# ClockRecovery.net
KiCad netlist of a schematic drawn in Altium Designer
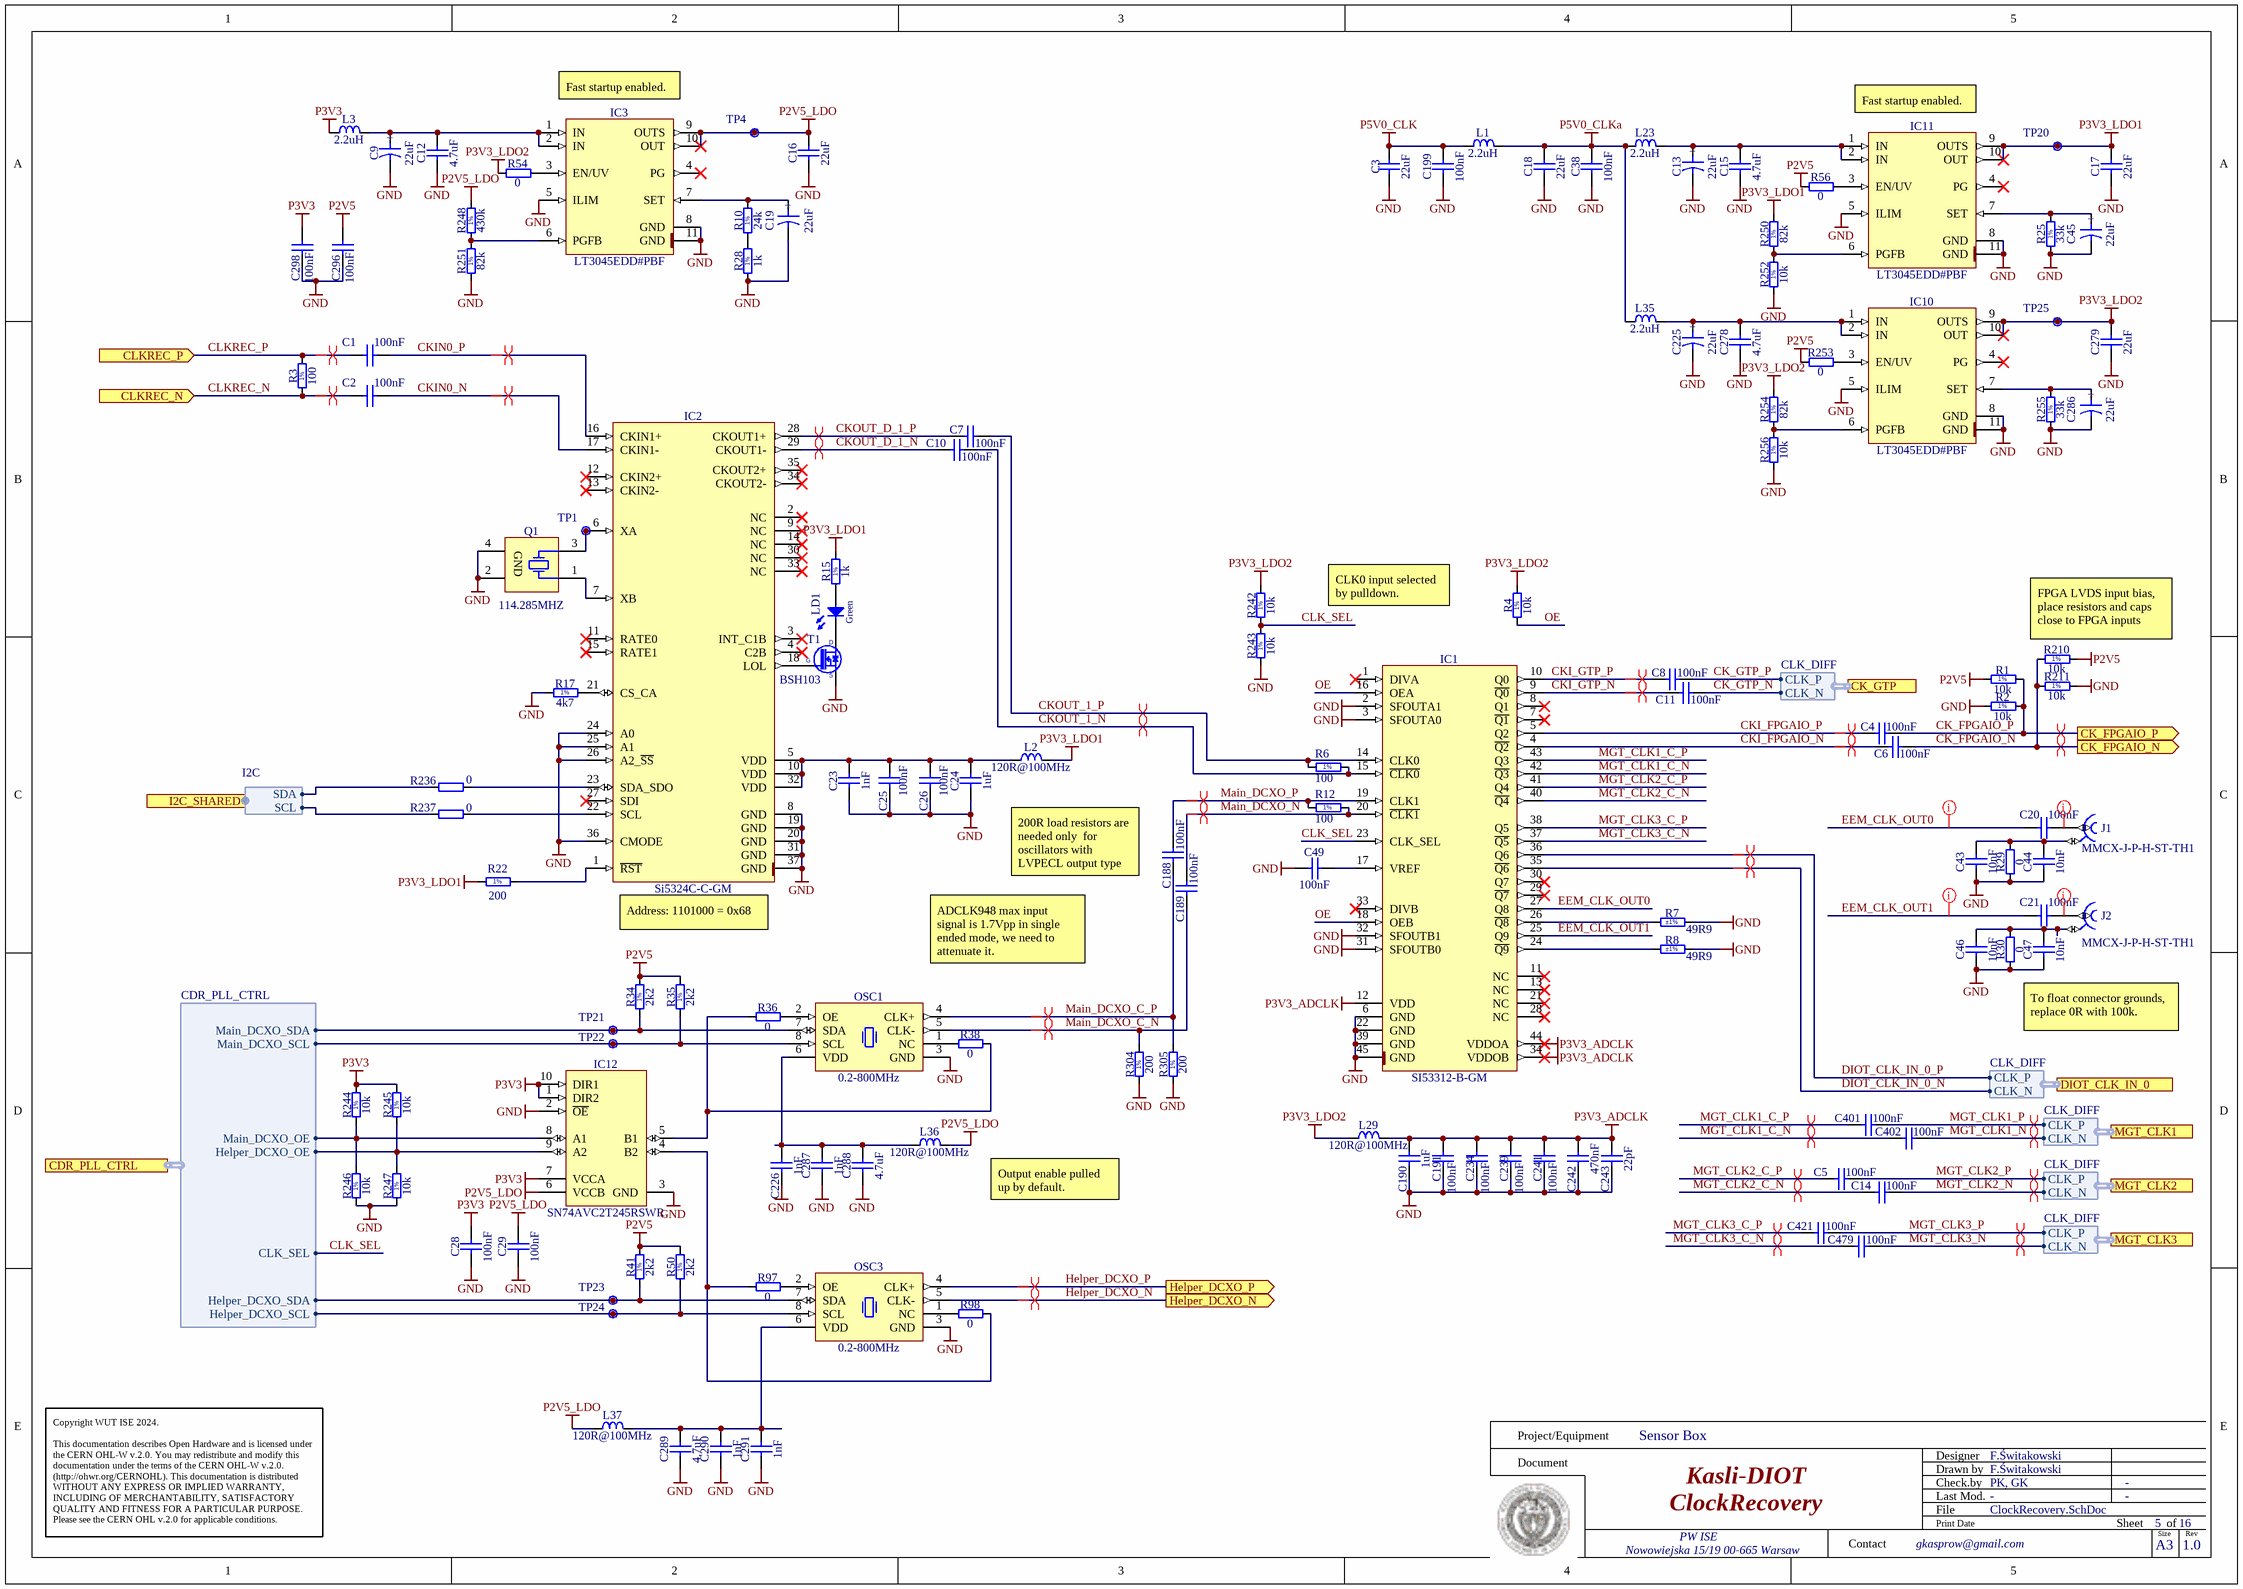
[diagram p0: ClockRecovery.SchDoc]

(export (version "E")
  (design (tool "Eeschema 10.0.6"))
  (components
    (comp (ref "C1")
      (value "100nF")
      (footprint "CAPC0603X33N")
      (description "Non-polarised capacitor")
      (fields
        (field (name "PART NUMBER") "CC0201_100NF_6.3V_10%_X5R")
        (field (name "VOLTAGE") "6.3V")
        (field (name "AUTHOR") "CERN DEM JLC")
      )
      (libsource (lib "Capacitors") (part "Capacitor - non polarized"))
    )
    (comp (ref "C2")
      (value "100nF")
      (footprint "CAPC0603X33N")
      (description "Non-polarised capacitor")
      (fields
        (field (name "PART NUMBER") "CC0201_100NF_6.3V_10%_X5R")
        (field (name "VOLTAGE") "6.3V")
        (field (name "AUTHOR") "CERN DEM JLC")
      )
      (libsource (lib "Capacitors") (part "Capacitor - non polarized"))
    )
    (comp (ref "C3")
      (value "22uF")
      (footprint "CAPC2012X135N")
      (description "Non-polarised capacitor")
      (fields
        (field (name "MANUFACTURER PART NUMBER") "CC0805_22UF_16V_10%_X5R")
        (field (name "MANUFACTURER") "GENERIC")
        (field (name "AUTHOR") "CERN DEM JLC")
      )
      (libsource (lib "Capacitors") (part "Capacitor - non polarized"))
    )
    (comp (ref "C4")
      (value "100nF")
      (footprint "CAPC0603X33N")
      (description "Non-polarised capacitor")
      (fields
        (field (name "PART NUMBER") "CC0201_100NF_6.3V_10%_X5R")
        (field (name "VOLTAGE") "6.3V")
        (field (name "AUTHOR") "CERN DEM JLC")
      )
      (libsource (lib "Capacitors") (part "Capacitor - non polarized"))
    )
    (comp (ref "C5")
      (value "100nF")
      (footprint "CAPC0603X33N")
      (description "Non-polarised capacitor")
      (fields
        (field (name "PART NUMBER") "CC0201_100NF_6.3V_10%_X5R")
        (field (name "VOLTAGE") "6.3V")
        (field (name "AUTHOR") "CERN DEM JLC")
      )
      (libsource (lib "Capacitors") (part "Capacitor - non polarized"))
    )
    (comp (ref "C6")
      (value "100nF")
      (footprint "CAPC0603X33N")
      (description "Non-polarised capacitor")
      (fields
        (field (name "PART NUMBER") "CC0201_100NF_6.3V_10%_X5R")
        (field (name "VOLTAGE") "6.3V")
        (field (name "AUTHOR") "CERN DEM JLC")
      )
      (libsource (lib "Capacitors") (part "Capacitor - non polarized"))
    )
    (comp (ref "C7")
      (value "100nF")
      (footprint "CAPC0603X33N")
      (description "Non-polarised capacitor")
      (fields
        (field (name "PART NUMBER") "CC0201_100NF_6.3V_10%_X5R")
        (field (name "VOLTAGE") "6.3V")
        (field (name "AUTHOR") "CERN DEM JLC")
      )
      (libsource (lib "Capacitors") (part "Capacitor - non polarized"))
    )
    (comp (ref "C8")
      (value "100nF")
      (footprint "CAPC0603X33N")
      (description "Non-polarised capacitor")
      (fields
        (field (name "PART NUMBER") "CC0201_100NF_6.3V_10%_X5R")
        (field (name "VOLTAGE") "6.3V")
        (field (name "AUTHOR") "CERN DEM JLC")
      )
      (libsource (lib "Capacitors") (part "Capacitor - non polarized"))
    )
    (comp (ref "C9")
      (value "22uF")
      (footprint "CAPMP3216X180N")
      (description "Polarised capacitor")
      (fields
        (field (name "PART NUMBER") "CTE3216-18_22UF_6.3V_10%_LESR0900")
        (field (name "VOLTAGE") "6.3V")
        (field (name "AUTHOR") "CERN DEM JLC")
      )
      (libsource (lib "Capacitors") (part "Capacitor - polarized"))
    )
    (comp (ref "C10")
      (value "100nF")
      (footprint "CAPC0603X33N")
      (description "Non-polarised capacitor")
      (fields
        (field (name "PART NUMBER") "CC0201_100NF_6.3V_10%_X5R")
        (field (name "VOLTAGE") "6.3V")
        (field (name "AUTHOR") "CERN DEM JLC")
      )
      (libsource (lib "Capacitors") (part "Capacitor - non polarized"))
    )
    (comp (ref "C11")
      (value "100nF")
      (footprint "CAPC0603X33N")
      (description "Non-polarised capacitor")
      (fields
        (field (name "PART NUMBER") "CC0201_100NF_6.3V_10%_X5R")
        (field (name "VOLTAGE") "6.3V")
        (field (name "AUTHOR") "CERN DEM JLC")
      )
      (libsource (lib "Capacitors") (part "Capacitor - non polarized"))
    )
    (comp (ref "C12")
      (value "4.7uF")
      (footprint "CAPC1005X55N")
      (description "Non-polarised capacitor")
      (fields
        (field (name "PART NUMBER") "CC0402_4.7UF_6.3V_20%_X5R")
        (field (name "VOLTAGE") "6.3V")
        (field (name "AUTHOR") "CERN DEM JLC")
      )
      (libsource (lib "Capacitors") (part "Capacitor - non polarized"))
    )
    (comp (ref "C13")
      (value "22uF")
      (footprint "CAPMP3216X180N")
      (description "Polarised capacitor")
      (fields
        (field (name "PART NUMBER") "CTE3216-18_22UF_6.3V_10%_LESR0900")
        (field (name "VOLTAGE") "6.3V")
        (field (name "AUTHOR") "CERN DEM JLC")
      )
      (libsource (lib "Capacitors") (part "Capacitor - polarized"))
    )
    (comp (ref "C14")
      (value "100nF")
      (footprint "CAPC0603X33N")
      (description "Non-polarised capacitor")
      (fields
        (field (name "PART NUMBER") "CC0201_100NF_6.3V_10%_X5R")
        (field (name "VOLTAGE") "6.3V")
        (field (name "AUTHOR") "CERN DEM JLC")
      )
      (libsource (lib "Capacitors") (part "Capacitor - non polarized"))
    )
    (comp (ref "C15")
      (value "4.7uF")
      (footprint "CAPC1005X55N")
      (description "Non-polarised capacitor")
      (fields
        (field (name "PART NUMBER") "CC0402_4.7UF_6.3V_20%_X5R")
        (field (name "VOLTAGE") "6.3V")
        (field (name "AUTHOR") "CERN DEM JLC")
      )
      (libsource (lib "Capacitors") (part "Capacitor - non polarized"))
    )
    (comp (ref "C16")
      (value "22uF")
      (footprint "CAPC1709X100N")
      (description "Non-polarised capacitor")
      (fields
        (field (name "PART NUMBER") "CC0603_22UF_6.3V_20%_X5R")
        (field (name "VOLTAGE") "6.3V")
        (field (name "AUTHOR") "CERN DEM JLC")
      )
      (libsource (lib "Capacitors") (part "Capacitor - non polarized"))
    )
    (comp (ref "C17")
      (value "22uF")
      (footprint "CAPC1709X100N")
      (description "Non-polarised capacitor")
      (fields
        (field (name "PART NUMBER") "CC0603_22UF_6.3V_20%_X5R")
        (field (name "VOLTAGE") "6.3V")
        (field (name "AUTHOR") "CERN DEM JLC")
      )
      (libsource (lib "Capacitors") (part "Capacitor - non polarized"))
    )
    (comp (ref "C18")
      (value "22uF")
      (footprint "CAPC2012X135N")
      (description "Non-polarised capacitor")
      (fields
        (field (name "MANUFACTURER PART NUMBER") "CC0805_22UF_16V_10%_X5R")
        (field (name "MANUFACTURER") "GENERIC")
        (field (name "AUTHOR") "CERN DEM JLC")
      )
      (libsource (lib "Capacitors") (part "Capacitor - non polarized"))
    )
    (comp (ref "C19")
      (value "22uF")
      (footprint "CAPMP3216X180N")
      (description "Polarised capacitor")
      (fields
        (field (name "PART NUMBER") "CTE3216-18_22UF_6.3V_10%_LESR0900")
        (field (name "VOLTAGE") "6.3V")
        (field (name "AUTHOR") "CERN DEM JLC")
      )
      (libsource (lib "Capacitors") (part "Capacitor - polarized"))
    )
    (comp (ref "C20")
      (value "100nF")
      (footprint "CAPC0603X33N")
      (description "Non-polarised capacitor")
      (fields
        (field (name "PART NUMBER") "CC0201_100NF_6.3V_10%_X5R")
        (field (name "VOLTAGE") "6.3V")
        (field (name "AUTHOR") "CERN DEM JLC")
      )
      (libsource (lib "Capacitors") (part "Capacitor - non polarized"))
    )
    (comp (ref "C21")
      (value "100nF")
      (footprint "CAPC0603X33N")
      (description "Non-polarised capacitor")
      (fields
        (field (name "PART NUMBER") "CC0201_100NF_6.3V_10%_X5R")
        (field (name "VOLTAGE") "6.3V")
        (field (name "AUTHOR") "CERN DEM JLC")
      )
      (libsource (lib "Capacitors") (part "Capacitor - non polarized"))
    )
    (comp (ref "C23")
      (value "1nF")
      (footprint "CAPC1005X55N")
      (description "Non-polarised capacitor")
      (fields
        (field (name "PART NUMBER") "CC0402_1NF_50V_10%_X7R")
        (field (name "VOLTAGE") "50V")
        (field (name "AUTHOR") "CERN DEM JLC")
      )
      (libsource (lib "Capacitors") (part "Capacitor - non polarized"))
    )
    (comp (ref "C24")
      (value "1uF")
      (footprint "CAPC1005X55N")
      (description "Non-polarised capacitor")
      (fields
        (field (name "PART NUMBER") "CC0402_1UF_16V_10%_X5R")
        (field (name "VOLTAGE") "16V")
        (field (name "AUTHOR") "CERN DEM JLC")
      )
      (libsource (lib "Capacitors") (part "Capacitor - non polarized"))
    )
    (comp (ref "C25")
      (value "100nF")
      (footprint "CAPC0603X33N")
      (description "Non-polarised capacitor")
      (fields
        (field (name "PART NUMBER") "CC0201_100NF_6.3V_10%_X5R")
        (field (name "VOLTAGE") "6.3V")
        (field (name "AUTHOR") "CERN DEM JLC")
      )
      (libsource (lib "Capacitors") (part "Capacitor - non polarized"))
    )
    (comp (ref "C26")
      (value "100nF")
      (footprint "CAPC0603X33N")
      (description "Non-polarised capacitor")
      (fields
        (field (name "PART NUMBER") "CC0201_100NF_6.3V_10%_X5R")
        (field (name "VOLTAGE") "6.3V")
        (field (name "AUTHOR") "CERN DEM JLC")
      )
      (libsource (lib "Capacitors") (part "Capacitor - non polarized"))
    )
    (comp (ref "C28")
      (value "100nF")
      (footprint "CAPC1005X55N")
      (description "Non-polarised capacitor")
      (fields
        (field (name "PART NUMBER") "CC0402_100NF_16V_10%_X7R")
        (field (name "VOLTAGE") "16V")
        (field (name "AUTHOR") "CERN DEM JLC")
      )
      (libsource (lib "Capacitors") (part "Capacitor - non polarized"))
    )
    (comp (ref "C29")
      (value "100nF")
      (footprint "CAPC1005X55N")
      (description "Non-polarised capacitor")
      (fields
        (field (name "PART NUMBER") "CC0402_100NF_16V_10%_X7R")
        (field (name "VOLTAGE") "16V")
        (field (name "AUTHOR") "CERN DEM JLC")
      )
      (libsource (lib "Capacitors") (part "Capacitor - non polarized"))
    )
    (comp (ref "C38")
      (value "100nF")
      (footprint "CAPC1005X55N")
      (description "Non-polarised capacitor")
      (fields
        (field (name "PART NUMBER") "CC0402_100NF_16V_10%_X7R")
        (field (name "VOLTAGE") "16V")
        (field (name "AUTHOR") "CERN DEM JLC")
      )
      (libsource (lib "Capacitors") (part "Capacitor - non polarized"))
    )
    (comp (ref "C43")
      (value "10nF")
      (footprint "CAPC1005X55N")
      (description "Non-polarised capacitor")
      (fields
        (field (name "PART NUMBER") "CC0402_10NF_16V_10%_X7R")
        (field (name "VOLTAGE") "16V")
        (field (name "AUTHOR") "CERN DEM JLC")
      )
      (libsource (lib "Capacitors") (part "Capacitor - non polarized"))
    )
    (comp (ref "C44")
      (value "10nF")
      (footprint "CAPC1005X55N")
      (description "Non-polarised capacitor")
      (fields
        (field (name "PART NUMBER") "CC0402_10NF_16V_10%_X7R")
        (field (name "VOLTAGE") "16V")
        (field (name "AUTHOR") "CERN DEM JLC")
      )
      (libsource (lib "Capacitors") (part "Capacitor - non polarized"))
    )
    (comp (ref "C45")
      (value "22uF")
      (footprint "CAPMP3216X180N")
      (description "Polarised capacitor")
      (fields
        (field (name "PART NUMBER") "CTE3216-18_22UF_6.3V_10%_LESR0900")
        (field (name "VOLTAGE") "6.3V")
        (field (name "AUTHOR") "CERN DEM JLC")
      )
      (libsource (lib "Capacitors") (part "Capacitor - polarized"))
    )
    (comp (ref "C46")
      (value "10nF")
      (footprint "CAPC1005X55N")
      (description "Non-polarised capacitor")
      (fields
        (field (name "PART NUMBER") "CC0402_10NF_16V_10%_X7R")
        (field (name "VOLTAGE") "16V")
        (field (name "AUTHOR") "CERN DEM JLC")
      )
      (libsource (lib "Capacitors") (part "Capacitor - non polarized"))
    )
    (comp (ref "C47")
      (value "10nF")
      (footprint "CAPC1005X55N")
      (description "Non-polarised capacitor")
      (fields
        (field (name "PART NUMBER") "CC0402_10NF_16V_10%_X7R")
        (field (name "VOLTAGE") "16V")
        (field (name "AUTHOR") "CERN DEM JLC")
      )
      (libsource (lib "Capacitors") (part "Capacitor - non polarized"))
    )
    (comp (ref "C49")
      (value "100nF")
      (footprint "CAPC1005X55N")
      (description "Non-polarised capacitor")
      (fields
        (field (name "PART NUMBER") "CC0402_100NF_16V_10%_X7R")
        (field (name "VOLTAGE") "16V")
        (field (name "AUTHOR") "CERN DEM JLC")
      )
      (libsource (lib "Capacitors") (part "Capacitor - non polarized"))
    )
    (comp (ref "C188")
      (value "100nF")
      (footprint "CAPC0603X33N")
      (description "Non-polarised capacitor")
      (fields
        (field (name "PART NUMBER") "CC0201_100NF_6.3V_10%_X5R")
        (field (name "VOLTAGE") "6.3V")
        (field (name "AUTHOR") "CERN DEM JLC")
      )
      (libsource (lib "Capacitors") (part "Capacitor - non polarized"))
    )
    (comp (ref "C189")
      (value "100nF")
      (footprint "CAPC0603X33N")
      (description "Non-polarised capacitor")
      (fields
        (field (name "PART NUMBER") "CC0201_100NF_6.3V_10%_X5R")
        (field (name "VOLTAGE") "6.3V")
        (field (name "AUTHOR") "CERN DEM JLC")
      )
      (libsource (lib "Capacitors") (part "Capacitor - non polarized"))
    )
    (comp (ref "C190")
      (value "1uF")
      (footprint "CAPC1005X55N")
      (description "Non-polarised capacitor")
      (fields
        (field (name "PART NUMBER") "CC0402_1UF_16V_10%_X5R")
        (field (name "VOLTAGE") "16V")
        (field (name "AUTHOR") "CERN DEM JLC")
      )
      (libsource (lib "Capacitors") (part "Capacitor - non polarized"))
    )
    (comp (ref "C191")
      (value "100nF")
      (footprint "CAPC1005X55N")
      (description "Non-polarised capacitor")
      (fields
        (field (name "PART NUMBER") "CC0402_100NF_16V_10%_X7R")
        (field (name "VOLTAGE") "16V")
        (field (name "AUTHOR") "CERN DEM JLC")
      )
      (libsource (lib "Capacitors") (part "Capacitor - non polarized"))
    )
    (comp (ref "C199")
      (value "100nF")
      (footprint "CAPC1005X55N")
      (description "Non-polarised capacitor")
      (fields
        (field (name "PART NUMBER") "CC0402_100NF_16V_10%_X7R")
        (field (name "VOLTAGE") "16V")
        (field (name "AUTHOR") "CERN DEM JLC")
      )
      (libsource (lib "Capacitors") (part "Capacitor - non polarized"))
    )
    (comp (ref "C225")
      (value "22uF")
      (footprint "CAPMP3216X180N")
      (description "Polarised capacitor")
      (fields
        (field (name "PART NUMBER") "CTE3216-18_22UF_6.3V_10%_LESR0900")
        (field (name "VOLTAGE") "6.3V")
        (field (name "AUTHOR") "CERN DEM JLC")
      )
      (libsource (lib "Capacitors") (part "Capacitor - polarized"))
    )
    (comp (ref "C226")
      (value "1nF")
      (footprint "CAPC1005X55N")
      (description "Non-polarised capacitor")
      (fields
        (field (name "PART NUMBER") "CC0402_1NF_50V_10%_X7R")
        (field (name "VOLTAGE") "50V")
        (field (name "AUTHOR") "CERN DEM JLC")
      )
      (libsource (lib "Capacitors") (part "Capacitor - non polarized"))
    )
    (comp (ref "C234")
      (value "100nF")
      (footprint "CAPC1005X55N")
      (description "Non-polarised capacitor")
      (fields
        (field (name "PART NUMBER") "CC0402_100NF_16V_10%_X7R")
        (field (name "VOLTAGE") "16V")
        (field (name "AUTHOR") "CERN DEM JLC")
      )
      (libsource (lib "Capacitors") (part "Capacitor - non polarized"))
    )
    (comp (ref "C239")
      (value "100nF")
      (footprint "CAPC1005X55N")
      (description "Non-polarised capacitor")
      (fields
        (field (name "PART NUMBER") "CC0402_100NF_16V_10%_X7R")
        (field (name "VOLTAGE") "16V")
        (field (name "AUTHOR") "CERN DEM JLC")
      )
      (libsource (lib "Capacitors") (part "Capacitor - non polarized"))
    )
    (comp (ref "C241")
      (value "100nF")
      (footprint "CAPC1005X55N")
      (description "Non-polarised capacitor")
      (fields
        (field (name "PART NUMBER") "CC0402_100NF_16V_10%_X7R")
        (field (name "VOLTAGE") "16V")
        (field (name "AUTHOR") "CERN DEM JLC")
      )
      (libsource (lib "Capacitors") (part "Capacitor - non polarized"))
    )
    (comp (ref "C242")
      (value "470nF")
      (footprint "CAPC0603X33N")
      (description "Non-polarised capacitor")
      (fields
        (field (name "PART NUMBER") "CC0201_470NF_4V_20%_X5R")
        (field (name "VOLTAGE") "4V")
        (field (name "AUTHOR") "CERN DEM JLC")
      )
      (libsource (lib "Capacitors") (part "Capacitor - non polarized"))
    )
    (comp (ref "C243")
      (value "22pF")
      (footprint "CAPC1005X55N")
      (description "Non-polarised capacitor")
      (fields
        (field (name "PART NUMBER") "CC0402_22PF_50V_5%_C0G")
        (field (name "VOLTAGE") "50V")
        (field (name "AUTHOR") "CERN DEM JLC")
      )
      (libsource (lib "Capacitors") (part "Capacitor - non polarized"))
    )
    (comp (ref "C278")
      (value "4.7uF")
      (footprint "CAPC1005X55N")
      (description "Non-polarised capacitor")
      (fields
        (field (name "PART NUMBER") "CC0402_4.7UF_6.3V_20%_X5R")
        (field (name "VOLTAGE") "6.3V")
        (field (name "AUTHOR") "CERN DEM JLC")
      )
      (libsource (lib "Capacitors") (part "Capacitor - non polarized"))
    )
    (comp (ref "C279")
      (value "22uF")
      (footprint "CAPC1709X100N")
      (description "Non-polarised capacitor")
      (fields
        (field (name "PART NUMBER") "CC0603_22UF_6.3V_20%_X5R")
        (field (name "VOLTAGE") "6.3V")
        (field (name "AUTHOR") "CERN DEM JLC")
      )
      (libsource (lib "Capacitors") (part "Capacitor - non polarized"))
    )
    (comp (ref "C286")
      (value "22uF")
      (footprint "CAPMP3216X180N")
      (description "Polarised capacitor")
      (fields
        (field (name "PART NUMBER") "CTE3216-18_22UF_6.3V_10%_LESR0900")
        (field (name "VOLTAGE") "6.3V")
        (field (name "AUTHOR") "CERN DEM JLC")
      )
      (libsource (lib "Capacitors") (part "Capacitor - polarized"))
    )
    (comp (ref "C287")
      (value "1nF")
      (footprint "CAPC1005X55N")
      (description "Non-polarised capacitor")
      (fields
        (field (name "PART NUMBER") "CC0402_1NF_50V_10%_X7R")
        (field (name "VOLTAGE") "50V")
        (field (name "AUTHOR") "CERN DEM JLC")
      )
      (libsource (lib "Capacitors") (part "Capacitor - non polarized"))
    )
    (comp (ref "C288")
      (value "4.7uF")
      (footprint "CAPC2012X135N")
      (description "Non-polarised capacitor")
      (fields
        (field (name "PART NUMBER") "CC0805_4.7UF_10V_10%_X5R")
        (field (name "VOLTAGE") "10V")
        (field (name "AUTHOR") "CERN DEM JLC")
      )
      (libsource (lib "Capacitors") (part "Capacitor - non polarized"))
    )
    (comp (ref "C289")
      (value "4.7uF")
      (footprint "CAPC2012X135N")
      (description "Non-polarised capacitor")
      (fields
        (field (name "PART NUMBER") "CC0805_4.7UF_10V_10%_X5R")
        (field (name "VOLTAGE") "10V")
        (field (name "AUTHOR") "CERN DEM JLC")
      )
      (libsource (lib "Capacitors") (part "Capacitor - non polarized"))
    )
    (comp (ref "C290")
      (value "1nF")
      (footprint "CAPC1005X55N")
      (description "Non-polarised capacitor")
      (fields
        (field (name "PART NUMBER") "CC0402_1NF_50V_10%_X7R")
        (field (name "VOLTAGE") "50V")
        (field (name "AUTHOR") "CERN DEM JLC")
      )
      (libsource (lib "Capacitors") (part "Capacitor - non polarized"))
    )
    (comp (ref "C291")
      (value "1nF")
      (footprint "CAPC1005X55N")
      (description "Non-polarised capacitor")
      (fields
        (field (name "PART NUMBER") "CC0402_1NF_50V_10%_X7R")
        (field (name "VOLTAGE") "50V")
        (field (name "AUTHOR") "CERN DEM JLC")
      )
      (libsource (lib "Capacitors") (part "Capacitor - non polarized"))
    )
    (comp (ref "C296")
      (value "100nF")
      (footprint "CAPC1005X55N")
      (description "Non-polarised capacitor")
      (fields
        (field (name "PART NUMBER") "CC0402_100NF_16V_10%_X7R")
        (field (name "VOLTAGE") "16V")
        (field (name "AUTHOR") "CERN DEM JLC")
      )
      (libsource (lib "Capacitors") (part "Capacitor - non polarized"))
    )
    (comp (ref "C298")
      (value "100nF")
      (footprint "CAPC1005X55N")
      (description "Non-polarised capacitor")
      (fields
        (field (name "PART NUMBER") "CC0402_100NF_16V_10%_X7R")
        (field (name "VOLTAGE") "16V")
        (field (name "AUTHOR") "CERN DEM JLC")
      )
      (libsource (lib "Capacitors") (part "Capacitor - non polarized"))
    )
    (comp (ref "C401")
      (value "100nF")
      (footprint "CAPC0603X33N")
      (description "Non-polarised capacitor")
      (fields
        (field (name "PART NUMBER") "CC0201_100NF_6.3V_10%_X5R")
        (field (name "VOLTAGE") "6.3V")
        (field (name "AUTHOR") "CERN DEM JLC")
      )
      (libsource (lib "Capacitors") (part "Capacitor - non polarized"))
    )
    (comp (ref "C402")
      (value "100nF")
      (footprint "CAPC0603X33N")
      (description "Non-polarised capacitor")
      (fields
        (field (name "PART NUMBER") "CC0201_100NF_6.3V_10%_X5R")
        (field (name "VOLTAGE") "6.3V")
        (field (name "AUTHOR") "CERN DEM JLC")
      )
      (libsource (lib "Capacitors") (part "Capacitor - non polarized"))
    )
    (comp (ref "C421")
      (value "100nF")
      (footprint "CAPC0603X33N")
      (description "Non-polarised capacitor")
      (fields
        (field (name "PART NUMBER") "CC0201_100NF_6.3V_10%_X5R")
        (field (name "VOLTAGE") "6.3V")
        (field (name "AUTHOR") "CERN DEM JLC")
      )
      (libsource (lib "Capacitors") (part "Capacitor - non polarized"))
    )
    (comp (ref "C479")
      (value "100nF")
      (footprint "CAPC0603X33N")
      (description "Non-polarised capacitor")
      (fields
        (field (name "PART NUMBER") "CC0201_100NF_6.3V_10%_X5R")
        (field (name "VOLTAGE") "6.3V")
        (field (name "AUTHOR") "CERN DEM JLC")
      )
      (libsource (lib "Capacitors") (part "Capacitor - non polarized"))
    )
    (comp (ref "IC1")
      (value "SI53312-B-GM")
      (footprint "QFN50P700X700X90-45N-S295")
      (description "2 Input/10 Output, Low Jitter Universal Buffer/Level Translator With 2:1 Input Mux (<1.25 GHZ)")
      (fields (field (name "MANUFACTURER") "SILICON LABS") (field (name "AUTHOR") "CERN DEM MR"))
      (libsource (lib "ICs And Semiconductors") (part "SI53312"))
    )
    (comp (ref "IC2")
      (value "Si5324C-C-GM")
      (footprint "QFN50P600X600X90-37N-S425")
      (description "Any Frequency Precision Clock Multiplier/Jitter Attenuator")
      (fields (field (name "MANUFACTURER") "SILICON LABS") (field (name "AUTHOR") "CERN DEM JLC"))
      (libsource (lib "ICs And Semiconductors") (part "Si5324"))
    )
    (comp (ref "IC3")
      (value "LT3045EDD#PBF")
      (footprint "SON50P300X300X80-11N-R175X248")
      (description "20V, 500mA, Ultralow Noise, Ultrahigh PSRR Linear Regulator")
      (fields (field (name "MANUFACTURER") "LINEAR TECHNOLOGY") (field (name "AUTHOR") "CERN DEM JLC"))
      (libsource (lib "ICs And Semiconductors") (part "LT3045EDD"))
    )
    (comp (ref "IC10")
      (value "LT3045EDD#PBF")
      (footprint "SON50P300X300X80-11N-R175X248")
      (description "20V, 500mA, Ultralow Noise, Ultrahigh PSRR Linear Regulator")
      (fields (field (name "MANUFACTURER") "LINEAR TECHNOLOGY") (field (name "AUTHOR") "CERN DEM JLC"))
      (libsource (lib "ICs And Semiconductors") (part "LT3045EDD"))
    )
    (comp (ref "IC11")
      (value "LT3045EDD#PBF")
      (footprint "SON50P300X300X80-11N-R175X248")
      (description "20V, 500mA, Ultralow Noise, Ultrahigh PSRR Linear Regulator")
      (fields (field (name "MANUFACTURER") "LINEAR TECHNOLOGY") (field (name "AUTHOR") "CERN DEM JLC"))
      (libsource (lib "ICs And Semiconductors") (part "LT3045EDD"))
    )
    (comp (ref "IC12")
      (value "SN74AVC2T245RSWR")
      (footprint "QFN40P140X180X55-10N")
      (description "Dual-Bit Dual-Supply Bus Transceiver With Configurable Voltage Translation and 3-State Outputs")
      (fields (field (name "MANUFACTURER") "TEXAS INSTRUMENTS") (field (name "AUTHOR") "CERN DEM JLC"))
      (libsource (lib "ICs And Semiconductors") (part "742T245"))
    )
    (comp (ref "J1")
      (value "MMCX-J-P-H-ST-TH1")
      (footprint "SAMTEC_MMCX-J-P-H-ST-TH1")
      (fields
        (field (name "PART NUMBER") "SAMTEC_MMCX-J-P-H-ST-TH1")
        (field (name "MANUFACTURER") "SAMTEC")
        (field (name "AUTHOR") "CERN DEM JLC")
      )
      (libsource (lib "Connectors") (part "Coax_1Female_1Shield"))
    )
    (comp (ref "J2")
      (value "MMCX-J-P-H-ST-TH1")
      (footprint "SAMTEC_MMCX-J-P-H-ST-TH1")
      (fields
        (field (name "PART NUMBER") "SAMTEC_MMCX-J-P-H-ST-TH1")
        (field (name "MANUFACTURER") "SAMTEC")
        (field (name "AUTHOR") "CERN DEM JLC")
      )
      (libsource (lib "Connectors") (part "Coax_1Female_1Shield"))
    )
    (comp (ref "L1")
      (value "2.2uH")
      (footprint "IND_WURTH_WE-PMCI_0806LR")
      (description "Inductor")
      (fields
        (field (name "MANUFACTURER PART NUMBER") "74479276222C")
        (field (name "MANUFACTURER") "WURTH ELEKTRONIK")
        (field (name "AUTHOR") "CERN DEM JLC")
      )
      (libsource (lib "Inductors & Transformers") (part "Inductor"))
    )
    (comp (ref "L2")
      (value "120R@100MHz")
      (footprint "INDC1608X65N")
      (description "Inductor")
      (fields
        (field (name "PART NUMBER") "IND0603_MURATA_BLM18SG121TN1D")
        (field (name "POWER") "3A")
        (field (name "AUTHOR") "CERN DEM JLC")
      )
      (libsource (lib "Inductors & Transformers") (part "Inductor"))
    )
    (comp (ref "L3")
      (value "2.2uH")
      (footprint "IND_WURTH_WE-PMCI_0806LR")
      (description "Inductor")
      (fields
        (field (name "PART NUMBER") "IND_2.2UH_20%_WURTH_WE-PMCI_74479276222C")
        (field (name "POWER") "1.1A")
        (field (name "AUTHOR") "CERN DEM JLC")
      )
      (libsource (lib "Inductors & Transformers") (part "Inductor"))
    )
    (comp (ref "L23")
      (value "2.2uH")
      (footprint "IND_WURTH_WE-PMCI_0806LR")
      (description "Inductor")
      (fields
        (field (name "PART NUMBER") "IND_2.2UH_20%_WURTH_WE-PMCI_74479276222C")
        (field (name "POWER") "1.1A")
        (field (name "AUTHOR") "CERN DEM JLC")
      )
      (libsource (lib "Inductors & Transformers") (part "Inductor"))
    )
    (comp (ref "L29")
      (value "120R@100MHz")
      (footprint "INDC1608X65N")
      (description "Inductor")
      (fields
        (field (name "PART NUMBER") "IND0603_MURATA_BLM18SG121TN1D")
        (field (name "POWER") "3A")
        (field (name "AUTHOR") "CERN DEM JLC")
      )
      (libsource (lib "") (part "Inductor_1"))
    )
    (comp (ref "L35")
      (value "2.2uH")
      (footprint "IND_WURTH_WE-PMCI_0806LR")
      (description "Inductor")
      (fields
        (field (name "PART NUMBER") "IND_2.2UH_20%_WURTH_WE-PMCI_74479276222C")
        (field (name "POWER") "1.1A")
        (field (name "AUTHOR") "CERN DEM JLC")
      )
      (libsource (lib "Inductors & Transformers") (part "Inductor"))
    )
    (comp (ref "L36")
      (value "120R@100MHz")
      (footprint "INDC1608X65N")
      (description "Inductor")
      (fields
        (field (name "PART NUMBER") "IND0603_MURATA_BLM18SG121TN1D")
        (field (name "POWER") "3A")
        (field (name "AUTHOR") "CERN DEM JLC")
      )
      (libsource (lib "") (part "Inductor_1"))
    )
    (comp (ref "L37")
      (value "120R@100MHz")
      (footprint "INDC1608X65N")
      (description "Inductor")
      (fields
        (field (name "PART NUMBER") "IND0603_MURATA_BLM18SG121TN1D")
        (field (name "POWER") "3A")
        (field (name "AUTHOR") "CERN DEM JLC")
      )
      (libsource (lib "Inductors & Transformers") (part "Inductor"))
    )
    (comp (ref "LD1")
      (value "Green")
      (footprint "LED_KINGBRIGHT_KPH-1608CGCK")
      (description "LED Green 1C 2A")
      (fields
        (field (name "MANUFACTURER PART NUMBER") "KPH-1608CGCK")
        (field (name "PART NUMBER") "LED_KINGBRIGHT_KPH-1608CGCK")
        (field (name "AUTHOR") "CERN DEM JLC")
      )
      (libsource (lib "ICs And Semiconductors") (part "LED Green 1C 2A"))
    )
    (comp (ref "OSC1")
      (value "0.2-800MHz")
      (footprint "OSC_SILICON-LAB_SI549-A")
      (description "Ultra Low Jitter I2C Programmable Crystal Oscillator (XO), Si549 Series")
      (fields
        (field (name "PART NUMBER") "OSC_0.2-800MHZ_SILICON-LAB_549BACB001937ABG")
        (field (name "MANUFACTURER") "SILICON LABS")
        (field (name "AUTHOR") "CERN DEM JMW")
      )
      (libsource (lib "ICs And Semiconductors") (part "Oscillator SILICON-LAB_Si549-CD"))
    )
    (comp (ref "OSC3")
      (value "0.2-800MHz")
      (footprint "OSC_SILICON-LAB_SI549-A")
      (description "Ultra Low Jitter I2C Programmable Crystal Oscillator (XO), Si549 Series")
      (fields
        (field (name "PART NUMBER") "OSC_0.2-800MHZ_SILICON-LAB_549BACB001937ABG")
        (field (name "MANUFACTURER") "SILICON LABS")
        (field (name "AUTHOR") "CERN DEM JMW")
      )
      (libsource (lib "ICs And Semiconductors") (part "Oscillator SILICON-LAB_Si549-CD"))
    )
    (comp (ref "Q1")
      (value "114.285MHZ")
      (footprint "XTAL_CONNOR_CS")
      (description "Crystal 4 pins 1=XTAL Control 2=GND3=XTAL 4=GND")
      (fields
        (field (name "PART NUMBER") "XTAL_114.285MHZ_CONNOR_CS-023")
        (field (name "MANUFACTURER") "CONNOR-WINFIELD")
        (field (name "AUTHOR") "CERN DEM JLC")
      )
      (libsource (lib "ICs And Semiconductors") (part "Quartz Crystal 1X 2GND 3X 4GND"))
    )
    (comp (ref "R1")
      (value "10k")
      (footprint "RESC1005X40N")
      (description "Resistor - 1%")
      (fields
        (field (name "PART NUMBER") "R0402_10K_1%_0.0625W_100PPM")
        (field (name "POWER") "0.0625W")
        (field (name "AUTHOR") "CERN DEM JLC")
      )
      (libsource (lib "Resistors") (part "Resistor - 1%"))
    )
    (comp (ref "R2")
      (value "10k")
      (footprint "RESC1005X40N")
      (description "Resistor - 1%")
      (fields
        (field (name "PART NUMBER") "R0402_10K_1%_0.0625W_100PPM")
        (field (name "POWER") "0.0625W")
        (field (name "AUTHOR") "CERN DEM JLC")
      )
      (libsource (lib "Resistors") (part "Resistor - 1%"))
    )
    (comp (ref "R3")
      (value "100")
      (footprint "RESC1005X40N")
      (description "Resistor - 1%")
      (fields
        (field (name "PART NUMBER") "R0402_100R_1%_0.0625W_100PPM")
        (field (name "POWER") "0.0625W")
        (field (name "AUTHOR") "CERN DEM JLC")
      )
      (libsource (lib "Resistors") (part "Resistor - 1%"))
    )
    (comp (ref "R4")
      (value "10k")
      (footprint "RESC1005X40N")
      (description "Resistor - 1%")
      (fields
        (field (name "PART NUMBER") "R0402_10K_1%_0.0625W_100PPM")
        (field (name "POWER") "0.0625W")
        (field (name "AUTHOR") "CERN DEM JLC")
      )
      (libsource (lib "Resistors") (part "Resistor - 1%"))
    )
    (comp (ref "R6")
      (value "100")
      (footprint "RESC1005X40N")
      (description "Resistor - 1%")
      (fields
        (field (name "PART NUMBER") "R0402_100R_1%_0.0625W_100PPM")
        (field (name "POWER") "0.0625W")
        (field (name "AUTHOR") "CERN DEM JLC")
      )
      (libsource (lib "Resistors") (part "Resistor - 1%"))
    )
    (comp (ref "R7")
      (value "49R9")
      (footprint "RESC1005X40N")
      (description "Resistor - 1%")
      (fields
        (field (name "TOLERANCE") "±1%")
        (field (name "PART NUMBER") "R0402_49R9_1%_0.0625W_100PPM")
        (field (name "POWER") "0.0625W")
        (field (name "AUTHOR") "CERN DEM JLC")
      )
      (libsource (lib "Resistors") (part "Resistor - 1%"))
    )
    (comp (ref "R8")
      (value "49R9")
      (footprint "RESC1005X40N")
      (description "Resistor - 1%")
      (fields
        (field (name "TOLERANCE") "±1%")
        (field (name "PART NUMBER") "R0402_49R9_1%_0.0625W_100PPM")
        (field (name "POWER") "0.0625W")
        (field (name "AUTHOR") "CERN DEM JLC")
      )
      (libsource (lib "Resistors") (part "Resistor - 1%"))
    )
    (comp (ref "R10")
      (value "24k")
      (footprint "RESC1005X40N")
      (description "Resistor - 1%")
      (fields
        (field (name "PART NUMBER") "R0402_24K_1%_0.0625W_100PPM")
        (field (name "POWER") "0.0625W")
        (field (name "AUTHOR") "CERN DEM JLC")
      )
      (libsource (lib "Resistors") (part "Resistor - 1%"))
    )
    (comp (ref "R12")
      (value "100")
      (footprint "RESC1005X40N")
      (description "Resistor - 1%")
      (fields
        (field (name "PART NUMBER") "R0402_100R_1%_0.0625W_100PPM")
        (field (name "POWER") "0.0625W")
        (field (name "AUTHOR") "CERN DEM JLC")
      )
      (libsource (lib "Resistors") (part "Resistor - 1%"))
    )
    (comp (ref "R15")
      (value "1k")
      (footprint "RESC1005X40N")
      (description "Resistor - 1%")
      (fields
        (field (name "PART NUMBER") "R0402_1K_1%_0.0625W_100PPM")
        (field (name "POWER") "0.0625W")
        (field (name "AUTHOR") "CERN DEM JLC")
      )
      (libsource (lib "Resistors") (part "Resistor - 1%"))
    )
    (comp (ref "R17")
      (value "4k7")
      (footprint "RESC1005X40N")
      (description "Resistor - 1%")
      (fields
        (field (name "PART NUMBER") "R0402_4K7_1%_0.0625W_100PPM")
        (field (name "POWER") "0.0625W")
        (field (name "AUTHOR") "CERN DEM JLC")
      )
      (libsource (lib "Resistors") (part "Resistor - 1%"))
    )
    (comp (ref "R22")
      (value "200")
      (footprint "RESC1005X40N")
      (description "Resistor - 1%")
      (fields
        (field (name "PART NUMBER") "R0402_200R_1%_0.0625W_100PPM")
        (field (name "POWER") "0.0625W")
        (field (name "AUTHOR") "CERN DEM JLC")
      )
      (libsource (lib "Resistors") (part "Resistor - 1%"))
    )
    (comp (ref "R25")
      (value "33k")
      (footprint "RESC1005X40N")
      (description "Resistor - 1%")
      (fields
        (field (name "PART NUMBER") "R0402_33K_1%_0.0625W_100PPM")
        (field (name "POWER") "0.0625W")
        (field (name "AUTHOR") "CERN DEM JLC")
      )
      (libsource (lib "Resistors") (part "Resistor - 1%"))
    )
    (comp (ref "R28")
      (value "1k")
      (footprint "RESC1005X40N")
      (description "Resistor - 1%")
      (fields
        (field (name "PART NUMBER") "R0402_1K_1%_0.0625W_100PPM")
        (field (name "POWER") "0.0625W")
        (field (name "AUTHOR") "CERN DEM JLC")
      )
      (libsource (lib "Resistors") (part "Resistor - 1%"))
    )
    (comp (ref "R29")
      (value "0")
      (footprint "RESC1005X40N")
      (description "Resistor")
      (fields
        (field (name "PART NUMBER") "R0402_0R_JUMPER")
        (field (name "MANUFACTURER") "GENERIC")
        (field (name "AUTHOR") "CERN DEM JLC")
      )
      (libsource (lib "Resistors") (part "Resistor"))
    )
    (comp (ref "R30")
      (value "0")
      (footprint "RESC1005X40N")
      (description "Resistor")
      (fields
        (field (name "PART NUMBER") "R0402_0R_JUMPER")
        (field (name "MANUFACTURER") "GENERIC")
        (field (name "AUTHOR") "CERN DEM JLC")
      )
      (libsource (lib "Resistors") (part "Resistor"))
    )
    (comp (ref "R34")
      (value "2k2")
      (footprint "RESC1005X40N")
      (description "Resistor - 1%")
      (fields
        (field (name "PART NUMBER") "R0402_2K2_1%_0.0625W_100PPM")
        (field (name "POWER") "0.0625W")
        (field (name "AUTHOR") "CERN DEM JLC")
      )
      (libsource (lib "Resistors") (part "Resistor - 1%"))
    )
    (comp (ref "R35")
      (value "2k2")
      (footprint "RESC1005X40N")
      (description "Resistor - 1%")
      (fields
        (field (name "PART NUMBER") "R0402_2K2_1%_0.0625W_100PPM")
        (field (name "POWER") "0.0625W")
        (field (name "AUTHOR") "CERN DEM JLC")
      )
      (libsource (lib "Resistors") (part "Resistor - 1%"))
    )
    (comp (ref "R36")
      (value "0")
      (footprint "RESC1005X40N")
      (description "Resistor")
      (fields
        (field (name "PART NUMBER") "R0402_0R_JUMPER")
        (field (name "MANUFACTURER") "GENERIC")
        (field (name "AUTHOR") "CERN DEM JLC")
      )
      (libsource (lib "Resistors") (part "Resistor"))
    )
    (comp (ref "R38")
      (value "0")
      (footprint "RESC1005X40N")
      (description "Resistor")
      (fields
        (field (name "PART NUMBER") "R0402_0R_JUMPER")
        (field (name "MANUFACTURER") "GENERIC")
        (field (name "AUTHOR") "CERN DEM JLC")
      )
      (libsource (lib "Resistors") (part "Resistor"))
    )
    (comp (ref "R41")
      (value "2k2")
      (footprint "RESC1005X40N")
      (description "Resistor - 1%")
      (fields
        (field (name "PART NUMBER") "R0402_2K2_1%_0.0625W_100PPM")
        (field (name "POWER") "0.0625W")
        (field (name "AUTHOR") "CERN DEM JLC")
      )
      (libsource (lib "Resistors") (part "Resistor - 1%"))
    )
    (comp (ref "R50")
      (value "2k2")
      (footprint "RESC1005X40N")
      (description "Resistor - 1%")
      (fields
        (field (name "PART NUMBER") "R0402_2K2_1%_0.0625W_100PPM")
        (field (name "POWER") "0.0625W")
        (field (name "AUTHOR") "CERN DEM JLC")
      )
      (libsource (lib "Resistors") (part "Resistor - 1%"))
    )
    (comp (ref "R54")
      (value "0")
      (footprint "RESC1005X40N")
      (description "Resistor")
      (fields
        (field (name "PART NUMBER") "R0402_0R_JUMPER")
        (field (name "MANUFACTURER") "GENERIC")
        (field (name "AUTHOR") "CERN DEM JLC")
      )
      (libsource (lib "Resistors") (part "Resistor"))
    )
    (comp (ref "R56")
      (value "0")
      (footprint "RESC1005X40N")
      (description "Resistor")
      (fields
        (field (name "PART NUMBER") "R0402_0R_JUMPER")
        (field (name "MANUFACTURER") "GENERIC")
        (field (name "AUTHOR") "CERN DEM JLC")
      )
      (libsource (lib "Resistors") (part "Resistor"))
    )
    (comp (ref "R97")
      (value "0")
      (footprint "RESC1005X40N")
      (description "Resistor")
      (fields
        (field (name "PART NUMBER") "R0402_0R_JUMPER")
        (field (name "MANUFACTURER") "GENERIC")
        (field (name "AUTHOR") "CERN DEM JLC")
      )
      (libsource (lib "Resistors") (part "Resistor"))
    )
    (comp (ref "R98")
      (value "0")
      (footprint "RESC1005X40N")
      (description "Resistor")
      (fields
        (field (name "PART NUMBER") "R0402_0R_JUMPER")
        (field (name "MANUFACTURER") "GENERIC")
        (field (name "AUTHOR") "CERN DEM JLC")
      )
      (libsource (lib "Resistors") (part "Resistor"))
    )
    (comp (ref "R210")
      (value "10k")
      (footprint "RESC1005X40N")
      (description "Resistor - 1%")
      (fields
        (field (name "PART NUMBER") "R0402_10K_1%_0.0625W_100PPM")
        (field (name "POWER") "0.0625W")
        (field (name "AUTHOR") "CERN DEM JLC")
      )
      (libsource (lib "Resistors") (part "Resistor - 1%"))
    )
    (comp (ref "R211")
      (value "10k")
      (footprint "RESC1005X40N")
      (description "Resistor - 1%")
      (fields
        (field (name "PART NUMBER") "R0402_10K_1%_0.0625W_100PPM")
        (field (name "POWER") "0.0625W")
        (field (name "AUTHOR") "CERN DEM JLC")
      )
      (libsource (lib "Resistors") (part "Resistor - 1%"))
    )
    (comp (ref "R236")
      (value "0")
      (footprint "RESC1005X40N")
      (description "Resistor")
      (fields
        (field (name "PART NUMBER") "R0402_0R_JUMPER")
        (field (name "MANUFACTURER") "GENERIC")
        (field (name "AUTHOR") "CERN DEM JLC")
      )
      (libsource (lib "Resistors") (part "Resistor"))
    )
    (comp (ref "R237")
      (value "0")
      (footprint "RESC1005X40N")
      (description "Resistor")
      (fields
        (field (name "PART NUMBER") "R0402_0R_JUMPER")
        (field (name "MANUFACTURER") "GENERIC")
        (field (name "AUTHOR") "CERN DEM JLC")
      )
      (libsource (lib "Resistors") (part "Resistor"))
    )
    (comp (ref "R242")
      (value "10k")
      (footprint "RESC1005X40N")
      (description "Resistor - 1%")
      (fields
        (field (name "PART NUMBER") "R0402_10K_1%_0.0625W_100PPM")
        (field (name "POWER") "0.0625W")
        (field (name "AUTHOR") "CERN DEM JLC")
      )
      (libsource (lib "Resistors") (part "Resistor - 1%"))
    )
    (comp (ref "R243")
      (value "10k")
      (footprint "RESC1005X40N")
      (description "Resistor - 1%")
      (fields
        (field (name "PART NUMBER") "R0402_10K_1%_0.0625W_100PPM")
        (field (name "POWER") "0.0625W")
        (field (name "AUTHOR") "CERN DEM JLC")
      )
      (libsource (lib "Resistors") (part "Resistor - 1%"))
    )
    (comp (ref "R244")
      (value "10k")
      (footprint "RESC1005X40N")
      (description "Resistor - 1%")
      (fields
        (field (name "PART NUMBER") "R0402_10K_1%_0.0625W_100PPM")
        (field (name "POWER") "0.0625W")
        (field (name "AUTHOR") "CERN DEM JLC")
      )
      (libsource (lib "Resistors") (part "Resistor - 1%"))
    )
    (comp (ref "R245")
      (value "10k")
      (footprint "RESC1005X40N")
      (description "Resistor - 1%")
      (fields
        (field (name "PART NUMBER") "R0402_10K_1%_0.0625W_100PPM")
        (field (name "POWER") "0.0625W")
        (field (name "AUTHOR") "CERN DEM JLC")
      )
      (libsource (lib "Resistors") (part "Resistor - 1%"))
    )
    (comp (ref "R246")
      (value "10k")
      (footprint "RESC1005X40N")
      (description "Resistor - 1%")
      (fields
        (field (name "PART NUMBER") "R0402_10K_1%_0.0625W_100PPM")
        (field (name "POWER") "0.0625W")
        (field (name "AUTHOR") "CERN DEM JLC")
      )
      (libsource (lib "Resistors") (part "Resistor - 1%"))
    )
    (comp (ref "R247")
      (value "10k")
      (footprint "RESC1005X40N")
      (description "Resistor - 1%")
      (fields
        (field (name "PART NUMBER") "R0402_10K_1%_0.0625W_100PPM")
        (field (name "POWER") "0.0625W")
        (field (name "AUTHOR") "CERN DEM JLC")
      )
      (libsource (lib "Resistors") (part "Resistor - 1%"))
    )
    (comp (ref "R248")
      (value "430k")
      (footprint "RESC1005X40N")
      (description "Resistor - 1%")
      (fields
        (field (name "MANUFACTURER PART NUMBER") "R0402_430K_1%_0.0625W_100PPM")
        (field (name "MANUFACTURER") "GENERIC")
        (field (name "AUTHOR") "CERN DEM JLC")
      )
      (libsource (lib "Resistors") (part "Resistor - 1%"))
    )
    (comp (ref "R250")
      (value "82k")
      (footprint "RESC1005X40N")
      (description "Resistor - 1%")
      (fields
        (field (name "MANUFACTURER PART NUMBER") "R0402_82K_1%_0.0625W_100PPM")
        (field (name "MANUFACTURER") "GENERIC")
        (field (name "AUTHOR") "CERN DEM JLC")
      )
      (libsource (lib "Resistors") (part "Resistor - 1%"))
    )
    (comp (ref "R251")
      (value "82k")
      (footprint "RESC1005X40N")
      (description "Resistor - 1%")
      (fields
        (field (name "PART NUMBER") "R0402_82K_1%_0.0625W_100PPM")
        (field (name "POWER") "0.0625W")
        (field (name "AUTHOR") "CERN DEM JLC")
      )
      (libsource (lib "Resistors") (part "Resistor - 1%"))
    )
    (comp (ref "R252")
      (value "10k")
      (footprint "RESC1005X40N")
      (description "Resistor - 1%")
      (fields
        (field (name "PART NUMBER") "R0402_10K_1%_0.0625W_100PPM")
        (field (name "POWER") "0.0625W")
        (field (name "AUTHOR") "CERN DEM JLC")
      )
      (libsource (lib "Resistors") (part "Resistor - 1%"))
    )
    (comp (ref "R253")
      (value "0")
      (footprint "RESC1005X40N")
      (description "Resistor")
      (fields
        (field (name "PART NUMBER") "R0402_0R_JUMPER")
        (field (name "MANUFACTURER") "GENERIC")
        (field (name "AUTHOR") "CERN DEM JLC")
      )
      (libsource (lib "Resistors") (part "Resistor"))
    )
    (comp (ref "R254")
      (value "82k")
      (footprint "RESC1005X40N")
      (description "Resistor - 1%")
      (fields
        (field (name "MANUFACTURER PART NUMBER") "R0402_82K_1%_0.0625W_100PPM")
        (field (name "MANUFACTURER") "GENERIC")
        (field (name "AUTHOR") "CERN DEM JLC")
      )
      (libsource (lib "Resistors") (part "Resistor - 1%"))
    )
    (comp (ref "R255")
      (value "33k")
      (footprint "RESC1005X40N")
      (description "Resistor - 1%")
      (fields
        (field (name "PART NUMBER") "R0402_33K_1%_0.0625W_100PPM")
        (field (name "POWER") "0.0625W")
        (field (name "AUTHOR") "CERN DEM JLC")
      )
      (libsource (lib "Resistors") (part "Resistor - 1%"))
    )
    (comp (ref "R256")
      (value "10k")
      (footprint "RESC1005X40N")
      (description "Resistor - 1%")
      (fields
        (field (name "PART NUMBER") "R0402_10K_1%_0.0625W_100PPM")
        (field (name "POWER") "0.0625W")
        (field (name "AUTHOR") "CERN DEM JLC")
      )
      (libsource (lib "Resistors") (part "Resistor - 1%"))
    )
    (comp (ref "R304")
      (value "200")
      (footprint "RESC1005X40N")
      (description "Resistor - 1%")
      (fields
        (field (name "PART NUMBER") "R0402_200R_1%_0.0625W_100PPM")
        (field (name "POWER") "0.0625W")
        (field (name "AUTHOR") "CERN DEM JLC")
      )
      (libsource (lib "Resistors") (part "Resistor - 1%"))
    )
    (comp (ref "R305")
      (value "200")
      (footprint "RESC1005X40N")
      (description "Resistor - 1%")
      (fields
        (field (name "PART NUMBER") "R0402_200R_1%_0.0625W_100PPM")
        (field (name "POWER") "0.0625W")
        (field (name "AUTHOR") "CERN DEM JLC")
      )
      (libsource (lib "Resistors") (part "Resistor - 1%"))
    )
    (comp (ref "T1")
      (value "BSH103")
      (footprint "SOT95P230X110-3N")
      (description "N-CHANNEL MOSFET WITH DIODE")
      (fields (field (name "MANUFACTURER") "NEXPERIA") (field (name "AUTHOR") "CERN DEM JLC"))
      (libsource (lib "ICs And Semiconductors") (part "N-MOSFET-D 1G 2S 3D"))
    )
    (comp (ref "TP1")
      (value "Test Point")
      (footprint "TPS127")
      (fields (field (name "PART NUMBER") "SMD_PAD_1.27X1.27MM") (field (name "AUTHOR") "CERN DEM JLC"))
      (libsource (lib "Eletro-mechanical") (part "Test Point"))
    )
    (comp (ref "TP4")
      (value "Test Point")
      (footprint "TPS127")
      (fields (field (name "PART NUMBER") "SMD_PAD_1.27X1.27MM") (field (name "AUTHOR") "CERN DEM JLC"))
      (libsource (lib "Eletro-mechanical") (part "Test Point"))
    )
    (comp (ref "TP20")
      (value "Test Point")
      (footprint "TPS127")
      (fields (field (name "PART NUMBER") "SMD_PAD_1.27X1.27MM") (field (name "AUTHOR") "CERN DEM JLC"))
      (libsource (lib "Eletro-mechanical") (part "Test Point"))
    )
    (comp (ref "TP21")
      (value "Test Point")
      (footprint "TPS127")
      (fields (field (name "PART NUMBER") "SMD_PAD_1.27X1.27MM") (field (name "AUTHOR") "CERN DEM JLC"))
      (libsource (lib "Eletro-mechanical") (part "Test Point"))
    )
    (comp (ref "TP22")
      (value "Test Point")
      (footprint "TPS127")
      (fields (field (name "PART NUMBER") "SMD_PAD_1.27X1.27MM") (field (name "AUTHOR") "CERN DEM JLC"))
      (libsource (lib "Eletro-mechanical") (part "Test Point"))
    )
    (comp (ref "TP23")
      (value "Test Point")
      (footprint "TPS127")
      (fields (field (name "PART NUMBER") "SMD_PAD_1.27X1.27MM") (field (name "AUTHOR") "CERN DEM JLC"))
      (libsource (lib "Eletro-mechanical") (part "Test Point"))
    )
    (comp (ref "TP24")
      (value "Test Point")
      (footprint "TPS127")
      (fields (field (name "PART NUMBER") "SMD_PAD_1.27X1.27MM") (field (name "AUTHOR") "CERN DEM JLC"))
      (libsource (lib "Eletro-mechanical") (part "Test Point"))
    )
    (comp (ref "TP25")
      (value "Test Point")
      (footprint "TPS127")
      (fields (field (name "PART NUMBER") "SMD_PAD_1.27X1.27MM") (field (name "AUTHOR") "CERN DEM JLC"))
      (libsource (lib "Eletro-mechanical") (part "Test Point"))
    )
  )
  (nets
    (net (code "4") (name "/CKIN0_N") (class "Default")
      (node (ref "C2") (pin "2") (pinfunction "2_2") (pintype "passive"))
      (node (ref "IC2") (pin "17") (pinfunction "CKIN1-_17") (pintype "input"))
    )
    (net (code "5") (name "/CKIN0_P") (class "Default")
      (node (ref "C1") (pin "2") (pinfunction "2_2") (pintype "passive"))
      (node (ref "IC2") (pin "16") (pinfunction "CKIN1+_16") (pintype "input"))
    )
    (net (code "6") (name "/CKI_FPGAIO_N") (class "Default")
      (node (ref "C6") (pin "1") (pinfunction "1_1") (pintype "passive"))
      (node (ref "IC1") (pin "4") (pinfunction "~{Q2}_4") (pintype "output"))
    )
    (net (code "7") (name "/CKI_FPGAIO_P") (class "Default")
      (node (ref "C4") (pin "1") (pinfunction "1_1") (pintype "passive"))
      (node (ref "IC1") (pin "5") (pinfunction "Q2_5") (pintype "output"))
    )
    (net (code "8") (name "/CKI_GTP_N") (class "Default")
      (node (ref "C11") (pin "1") (pinfunction "1_1") (pintype "passive"))
      (node (ref "IC1") (pin "9") (pinfunction "~{Q0}_9") (pintype "output"))
    )
    (net (code "9") (name "/CKI_GTP_P") (class "Default")
      (node (ref "C8") (pin "1") (pinfunction "1_1") (pintype "passive"))
      (node (ref "IC1") (pin "10") (pinfunction "Q0_10") (pintype "output"))
    )
    (net (code "10") (name "/CKOUT_1_N") (class "Default")
      (node (ref "C10") (pin "2") (pinfunction "2_2") (pintype "passive"))
      (node (ref "IC1") (pin "15") (pinfunction "~{CLK0}_15") (pintype "input"))
      (node (ref "R6") (pin "2") (pinfunction "2_2") (pintype "passive"))
    )
    (net (code "11") (name "/CKOUT_1_P") (class "Default")
      (node (ref "C7") (pin "2") (pinfunction "2_2") (pintype "passive"))
      (node (ref "IC1") (pin "14") (pinfunction "CLK0_14") (pintype "input"))
      (node (ref "R6") (pin "1") (pinfunction "1_1") (pintype "passive"))
    )
    (net (code "12") (name "/CKOUT_D_1_N") (class "Default")
      (node (ref "C10") (pin "1") (pinfunction "1_1") (pintype "passive"))
      (node (ref "IC2") (pin "29") (pinfunction "CKOUT1-_29") (pintype "output"))
    )
    (net (code "13") (name "/CKOUT_D_1_P") (class "Default")
      (node (ref "C7") (pin "1") (pinfunction "1_1") (pintype "passive"))
      (node (ref "IC2") (pin "28") (pinfunction "CKOUT1+_28") (pintype "output"))
    )
    (net (code "14") (name "/CK_FPGAIO_N") (class "Default")
      (node (ref "C6") (pin "2") (pinfunction "2_2") (pintype "passive"))
      (node (ref "R210") (pin "2") (pinfunction "2_2") (pintype "passive"))
      (node (ref "R211") (pin "2") (pinfunction "2_2") (pintype "passive"))
    )
    (net (code "15") (name "/CK_FPGAIO_P") (class "Default")
      (node (ref "C4") (pin "2") (pinfunction "2_2") (pintype "passive"))
      (node (ref "R1") (pin "2") (pinfunction "2_2") (pintype "passive"))
      (node (ref "R2") (pin "2") (pinfunction "2_2") (pintype "passive"))
    )
    (net (code "16") (name "/CK_GTP_N") (class "Default")
      (node (ref "C11") (pin "2") (pinfunction "2_2") (pintype "passive"))
    )
    (net (code "17") (name "/CK_GTP_P") (class "Default")
      (node (ref "C8") (pin "2") (pinfunction "2_2") (pintype "passive"))
    )
    (net (code "18") (name "/CLKREC_N") (class "Default")
      (node (ref "C2") (pin "1") (pinfunction "1_1") (pintype "passive"))
      (node (ref "R3") (pin "1") (pinfunction "1_1") (pintype "passive"))
    )
    (net (code "19") (name "/CLKREC_P") (class "Default")
      (node (ref "C1") (pin "1") (pinfunction "1_1") (pintype "passive"))
      (node (ref "R3") (pin "2") (pinfunction "2_2") (pintype "passive"))
    )
    (net (code "20") (name "/CLK_SEL") (class "Default")
      (node (ref "IC1") (pin "23") (pinfunction "CLK_SEL_23") (pintype "input"))
      (node (ref "R242") (pin "1") (pinfunction "1_1") (pintype "passive"))
      (node (ref "R243") (pin "2") (pinfunction "2_2") (pintype "passive"))
    )
    (net (code "21") (name "/DIOT_CLK_IN_0_N") (class "Default")
      (node (ref "IC1") (pin "35") (pinfunction "~{Q6}_35") (pintype "output"))
    )
    (net (code "22") (name "/DIOT_CLK_IN_0_P") (class "Default")
      (node (ref "IC1") (pin "36") (pinfunction "Q6_36") (pintype "output"))
    )
    (net (code "23") (name "/EEM_CLK_OUT0") (class "Default")
      (node (ref "C20") (pin "1") (pinfunction "1_1") (pintype "passive"))
      (node (ref "IC1") (pin "27") (pinfunction "Q8_27") (pintype "output"))
    )
    (net (code "24") (name "/EEM_CLK_OUT1") (class "Default")
      (node (ref "C21") (pin "1") (pinfunction "1_1") (pintype "passive"))
      (node (ref "IC1") (pin "25") (pinfunction "Q9_25") (pintype "output"))
    )
    (net (code "25") (name "/Helper_DCXO_N") (class "Default")
      (node (ref "OSC3") (pin "5") (pinfunction "CLK-_5") (pintype "output"))
    )
    (net (code "26") (name "/Helper_DCXO_OE") (class "Default")
      (node (ref "IC12") (pin "9") (pinfunction "A2_9") (pintype "bidirectional"))
      (node (ref "R245") (pin "1") (pinfunction "1_1") (pintype "passive"))
      (node (ref "R247") (pin "2") (pinfunction "2_2") (pintype "passive"))
    )
    (net (code "27") (name "/Helper_DCXO_P") (class "Default")
      (node (ref "OSC3") (pin "4") (pinfunction "CLK+_4") (pintype "output"))
    )
    (net (code "28") (name "/Helper_DCXO_SCL") (class "Default")
      (node (ref "OSC3") (pin "8") (pinfunction "SCL_8") (pintype "input"))
      (node (ref "R50") (pin "1") (pinfunction "1_1") (pintype "passive"))
      (node (ref "TP24") (pin "1") (pinfunction "1_1") (pintype "bidirectional"))
    )
    (net (code "29") (name "/Helper_DCXO_SDA") (class "Default")
      (node (ref "OSC3") (pin "7") (pinfunction "SDA_7") (pintype "bidirectional"))
      (node (ref "R41") (pin "1") (pinfunction "1_1") (pintype "passive"))
      (node (ref "TP23") (pin "1") (pinfunction "1_1") (pintype "bidirectional"))
    )
    (net (code "30") (name "/MGT_CLK1_C_N") (class "Default")
      (node (ref "C402") (pin "1") (pinfunction "1_1") (pintype "passive"))
      (node (ref "IC1") (pin "42") (pinfunction "~{Q3}_42") (pintype "output"))
    )
    (net (code "31") (name "/MGT_CLK1_C_P") (class "Default")
      (node (ref "C401") (pin "1") (pinfunction "1_1") (pintype "passive"))
      (node (ref "IC1") (pin "43") (pinfunction "Q3_43") (pintype "output"))
    )
    (net (code "32") (name "/MGT_CLK1_N") (class "Default")
      (node (ref "C402") (pin "2") (pinfunction "2_2") (pintype "passive"))
    )
    (net (code "33") (name "/MGT_CLK1_P") (class "Default")
      (node (ref "C401") (pin "2") (pinfunction "2_2") (pintype "passive"))
    )
    (net (code "34") (name "/MGT_CLK2_C_N") (class "Default")
      (node (ref "C14") (pin "1") (pinfunction "1_1") (pintype "passive"))
      (node (ref "IC1") (pin "40") (pinfunction "~{Q4}_40") (pintype "output"))
    )
    (net (code "35") (name "/MGT_CLK2_C_P") (class "Default")
      (node (ref "C5") (pin "1") (pinfunction "1_1") (pintype "passive"))
      (node (ref "IC1") (pin "41") (pinfunction "Q4_41") (pintype "output"))
    )
    (net (code "36") (name "/MGT_CLK2_N") (class "Default")
      (node (ref "C14") (pin "2") (pinfunction "2_2") (pintype "passive"))
    )
    (net (code "37") (name "/MGT_CLK2_P") (class "Default")
      (node (ref "C5") (pin "2") (pinfunction "2_2") (pintype "passive"))
    )
    (net (code "38") (name "/MGT_CLK3_C_N") (class "Default")
      (node (ref "C479") (pin "1") (pinfunction "1_1") (pintype "passive"))
      (node (ref "IC1") (pin "37") (pinfunction "~{Q5}_37") (pintype "output"))
    )
    (net (code "39") (name "/MGT_CLK3_C_P") (class "Default")
      (node (ref "C421") (pin "1") (pinfunction "1_1") (pintype "passive"))
      (node (ref "IC1") (pin "38") (pinfunction "Q5_38") (pintype "output"))
    )
    (net (code "40") (name "/MGT_CLK3_N") (class "Default")
      (node (ref "C479") (pin "2") (pinfunction "2_2") (pintype "passive"))
    )
    (net (code "41") (name "/MGT_CLK3_P") (class "Default")
      (node (ref "C421") (pin "2") (pinfunction "2_2") (pintype "passive"))
    )
    (net (code "42") (name "/Main_DCXO_C_N") (class "Default")
      (node (ref "C189") (pin "1") (pinfunction "1_1") (pintype "passive"))
      (node (ref "OSC1") (pin "5") (pinfunction "CLK-_5") (pintype "output"))
      (node (ref "R304") (pin "2") (pinfunction "2_2") (pintype "passive"))
    )
    (net (code "43") (name "/Main_DCXO_C_P") (class "Default")
      (node (ref "C188") (pin "1") (pinfunction "1_1") (pintype "passive"))
      (node (ref "OSC1") (pin "4") (pinfunction "CLK+_4") (pintype "output"))
      (node (ref "R305") (pin "2") (pinfunction "2_2") (pintype "passive"))
    )
    (net (code "44") (name "/Main_DCXO_N") (class "Default")
      (node (ref "C189") (pin "2") (pinfunction "2_2") (pintype "passive"))
      (node (ref "IC1") (pin "20") (pinfunction "~{CLK1}_20") (pintype "input"))
      (node (ref "R12") (pin "2") (pinfunction "2_2") (pintype "passive"))
    )
    (net (code "45") (name "/Main_DCXO_OE") (class "Default")
      (node (ref "IC12") (pin "8") (pinfunction "A1_8") (pintype "bidirectional"))
      (node (ref "R244") (pin "1") (pinfunction "1_1") (pintype "passive"))
      (node (ref "R246") (pin "2") (pinfunction "2_2") (pintype "passive"))
    )
    (net (code "46") (name "/Main_DCXO_P") (class "Default")
      (node (ref "C188") (pin "2") (pinfunction "2_2") (pintype "passive"))
      (node (ref "IC1") (pin "19") (pinfunction "CLK1_19") (pintype "input"))
      (node (ref "R12") (pin "1") (pinfunction "1_1") (pintype "passive"))
    )
    (net (code "47") (name "/Main_DCXO_SCL") (class "Default")
      (node (ref "OSC1") (pin "8") (pinfunction "SCL_8") (pintype "input"))
      (node (ref "R35") (pin "1") (pinfunction "1_1") (pintype "passive"))
      (node (ref "TP22") (pin "1") (pinfunction "1_1") (pintype "bidirectional"))
    )
    (net (code "48") (name "/Main_DCXO_SDA") (class "Default")
      (node (ref "OSC1") (pin "7") (pinfunction "SDA_7") (pintype "bidirectional"))
      (node (ref "R34") (pin "1") (pinfunction "1_1") (pintype "passive"))
      (node (ref "TP21") (pin "1") (pinfunction "1_1") (pintype "bidirectional"))
    )
    (net (code "49") (name "/OE") (class "Default")
      (node (ref "IC1") (pin "16") (pinfunction "OEA_16") (pintype "input"))
      (node (ref "IC1") (pin "18") (pinfunction "OEB_18") (pintype "input"))
      (node (ref "R4") (pin "1") (pinfunction "1_1") (pintype "passive"))
    )
    (net (code "50") (name "/SCL") (class "Default")
      (node (ref "R237") (pin "1") (pinfunction "1_1") (pintype "passive"))
    )
    (net (code "51") (name "/SDA") (class "Default")
      (node (ref "R236") (pin "1") (pinfunction "1_1") (pintype "passive"))
    )
    (net (code "55") (name "GND") (class "Default")
      (node (ref "C12") (pin "1") (pinfunction "1_1") (pintype "passive"))
      (node (ref "C13") (pin "2") (pinfunction "2_2") (pintype "passive"))
      (node (ref "C15") (pin "1") (pinfunction "1_1") (pintype "passive"))
      (node (ref "C16") (pin "1") (pinfunction "1_1") (pintype "passive"))
      (node (ref "C17") (pin "1") (pinfunction "1_1") (pintype "passive"))
      (node (ref "C18") (pin "1") (pinfunction "1_1") (pintype "passive"))
      (node (ref "C19") (pin "2") (pinfunction "2_2") (pintype "passive"))
      (node (ref "C190") (pin "1") (pinfunction "1_1") (pintype "passive"))
      (node (ref "C191") (pin "1") (pinfunction "1_1") (pintype "passive"))
      (node (ref "C199") (pin "1") (pinfunction "1_1") (pintype "passive"))
      (node (ref "C225") (pin "2") (pinfunction "2_2") (pintype "passive"))
      (node (ref "C226") (pin "1") (pinfunction "1_1") (pintype "passive"))
      (node (ref "C23") (pin "1") (pinfunction "1_1") (pintype "passive"))
      (node (ref "C234") (pin "1") (pinfunction "1_1") (pintype "passive"))
      (node (ref "C239") (pin "1") (pinfunction "1_1") (pintype "passive"))
      (node (ref "C24") (pin "1") (pinfunction "1_1") (pintype "passive"))
      (node (ref "C241") (pin "1") (pinfunction "1_1") (pintype "passive"))
      (node (ref "C242") (pin "1") (pinfunction "1_1") (pintype "passive"))
      (node (ref "C243") (pin "1") (pinfunction "1_1") (pintype "passive"))
      (node (ref "C25") (pin "1") (pinfunction "1_1") (pintype "passive"))
      (node (ref "C26") (pin "1") (pinfunction "1_1") (pintype "passive"))
      (node (ref "C278") (pin "1") (pinfunction "1_1") (pintype "passive"))
      (node (ref "C279") (pin "1") (pinfunction "1_1") (pintype "passive"))
      (node (ref "C28") (pin "1") (pinfunction "1_1") (pintype "passive"))
      (node (ref "C286") (pin "2") (pinfunction "2_2") (pintype "passive"))
      (node (ref "C287") (pin "1") (pinfunction "1_1") (pintype "passive"))
      (node (ref "C288") (pin "1") (pinfunction "1_1") (pintype "passive"))
      (node (ref "C289") (pin "1") (pinfunction "1_1") (pintype "passive"))
      (node (ref "C29") (pin "1") (pinfunction "1_1") (pintype "passive"))
      (node (ref "C290") (pin "1") (pinfunction "1_1") (pintype "passive"))
      (node (ref "C291") (pin "1") (pinfunction "1_1") (pintype "passive"))
      (node (ref "C296") (pin "1") (pinfunction "1_1") (pintype "passive"))
      (node (ref "C298") (pin "1") (pinfunction "1_1") (pintype "passive"))
      (node (ref "C3") (pin "1") (pinfunction "1_1") (pintype "passive"))
      (node (ref "C38") (pin "1") (pinfunction "1_1") (pintype "passive"))
      (node (ref "C43") (pin "1") (pinfunction "1_1") (pintype "passive"))
      (node (ref "C44") (pin "1") (pinfunction "1_1") (pintype "passive"))
      (node (ref "C45") (pin "2") (pinfunction "2_2") (pintype "passive"))
      (node (ref "C46") (pin "1") (pinfunction "1_1") (pintype "passive"))
      (node (ref "C47") (pin "1") (pinfunction "1_1") (pintype "passive"))
      (node (ref "C49") (pin "1") (pinfunction "1_1") (pintype "passive"))
      (node (ref "C9") (pin "2") (pinfunction "2_2") (pintype "passive"))
      (node (ref "IC1") (pin "2") (pinfunction "SFOUTA1_2") (pintype "input"))
      (node (ref "IC1") (pin "22") (pinfunction "GND_22") (pintype "power_in"))
      (node (ref "IC1") (pin "3") (pinfunction "SFOUTA0_3") (pintype "input"))
      (node (ref "IC1") (pin "31") (pinfunction "SFOUTB0_31") (pintype "input"))
      (node (ref "IC1") (pin "32") (pinfunction "SFOUTB1_32") (pintype "input"))
      (node (ref "IC1") (pin "39") (pinfunction "GND_39") (pintype "power_in"))
      (node (ref "IC1") (pin "45") (pinfunction "GND_45") (pintype "power_in"))
      (node (ref "IC1") (pin "6") (pinfunction "GND_6") (pintype "power_in"))
      (node (ref "IC10") (pin "11") (pinfunction "GND_11") (pintype "power_in"))
      (node (ref "IC10") (pin "5") (pinfunction "ILIM_5") (pintype "input"))
      (node (ref "IC10") (pin "8") (pinfunction "GND_8") (pintype "power_in"))
      (node (ref "IC11") (pin "11") (pinfunction "GND_11") (pintype "power_in"))
      (node (ref "IC11") (pin "5") (pinfunction "ILIM_5") (pintype "input"))
      (node (ref "IC11") (pin "8") (pinfunction "GND_8") (pintype "power_in"))
      (node (ref "IC12") (pin "2") (pinfunction "~{OE}_2") (pintype "input"))
      (node (ref "IC12") (pin "3") (pinfunction "GND_3") (pintype "power_in"))
      (node (ref "IC2") (pin "19") (pinfunction "GND_19") (pintype "power_in"))
      (node (ref "IC2") (pin "20") (pinfunction "GND_20") (pintype "power_in"))
      (node (ref "IC2") (pin "24") (pinfunction "A0_24") (pintype "input"))
      (node (ref "IC2") (pin "25") (pinfunction "A1_25") (pintype "input"))
      (node (ref "IC2") (pin "26") (pinfunction "A2_~{SS}_26") (pintype "input"))
      (node (ref "IC2") (pin "31") (pinfunction "GND_31") (pintype "power_in"))
      (node (ref "IC2") (pin "36") (pinfunction "CMODE_36") (pintype "input"))
      (node (ref "IC2") (pin "37") (pinfunction "GND_37") (pintype "power_in"))
      (node (ref "IC2") (pin "8") (pinfunction "GND_8") (pintype "power_in"))
      (node (ref "IC3") (pin "11") (pinfunction "GND_11") (pintype "power_in"))
      (node (ref "IC3") (pin "5") (pinfunction "ILIM_5") (pintype "input"))
      (node (ref "IC3") (pin "8") (pinfunction "GND_8") (pintype "power_in"))
      (node (ref "OSC1") (pin "3") (pinfunction "GND_3") (pintype "power_in"))
      (node (ref "OSC3") (pin "3") (pinfunction "GND_3") (pintype "power_in"))
      (node (ref "Q1") (pin "2") (pinfunction "GND_2") (pintype "power_in"))
      (node (ref "Q1") (pin "4") (pinfunction "GND_4") (pintype "power_in"))
      (node (ref "R17") (pin "1") (pinfunction "1_1") (pintype "passive"))
      (node (ref "R2") (pin "1") (pinfunction "1_1") (pintype "passive"))
      (node (ref "R211") (pin "1") (pinfunction "1_1") (pintype "passive"))
      (node (ref "R243") (pin "1") (pinfunction "1_1") (pintype "passive"))
      (node (ref "R246") (pin "1") (pinfunction "1_1") (pintype "passive"))
      (node (ref "R247") (pin "1") (pinfunction "1_1") (pintype "passive"))
      (node (ref "R25") (pin "1") (pinfunction "1_1") (pintype "passive"))
      (node (ref "R251") (pin "1") (pinfunction "1_1") (pintype "passive"))
      (node (ref "R252") (pin "2") (pinfunction "2_2") (pintype "passive"))
      (node (ref "R255") (pin "1") (pinfunction "1_1") (pintype "passive"))
      (node (ref "R256") (pin "2") (pinfunction "2_2") (pintype "passive"))
      (node (ref "R28") (pin "1") (pinfunction "1_1") (pintype "passive"))
      (node (ref "R29") (pin "1") (pinfunction "1_1") (pintype "passive"))
      (node (ref "R30") (pin "1") (pinfunction "1_1") (pintype "passive"))
      (node (ref "R304") (pin "1") (pinfunction "1_1") (pintype "passive"))
      (node (ref "R305") (pin "1") (pinfunction "1_1") (pintype "passive"))
      (node (ref "R7") (pin "2") (pinfunction "2_2") (pintype "passive"))
      (node (ref "R8") (pin "2") (pinfunction "2_2") (pintype "passive"))
      (node (ref "T1") (pin "2") (pinfunction "S_2") (pintype "passive"))
    )
    (net (code "56") (name "Net-(C12-Pad2)") (class "Default")
      (node (ref "C12") (pin "2") (pinfunction "2_2") (pintype "passive"))
      (node (ref "C9") (pin "1") (pinfunction "1_1") (pintype "passive"))
      (node (ref "IC3") (pin "1") (pinfunction "IN_1") (pintype "input"))
      (node (ref "IC3") (pin "2") (pinfunction "IN_2") (pintype "input"))
      (node (ref "L3") (pin "2") (pinfunction "2_2") (pintype "passive"))
    )
    (net (code "57") (name "Net-(C13-Pad1)") (class "Default")
      (node (ref "C13") (pin "1") (pinfunction "1_1") (pintype "passive"))
      (node (ref "C15") (pin "2") (pinfunction "2_2") (pintype "passive"))
      (node (ref "IC11") (pin "1") (pinfunction "IN_1") (pintype "input"))
      (node (ref "IC11") (pin "2") (pinfunction "IN_2") (pintype "input"))
      (node (ref "L23") (pin "2") (pinfunction "2_2") (pintype "passive"))
    )
    (net (code "58") (name "Net-(C20-Pad2)") (class "Default")
      (node (ref "C20") (pin "2") (pinfunction "2_2") (pintype "passive"))
      (node (ref "J1") (pin "1") (pinfunction "1_1") (pintype "bidirectional"))
    )
    (net (code "59") (name "Net-(C21-Pad2)") (class "Default")
      (node (ref "C21") (pin "2") (pinfunction "2_2") (pintype "passive"))
      (node (ref "J2") (pin "1") (pinfunction "1_1") (pintype "bidirectional"))
    )
    (net (code "60") (name "Net-(C23-Pad2)") (class "Default")
      (node (ref "C23") (pin "2") (pinfunction "2_2") (pintype "passive"))
      (node (ref "C24") (pin "2") (pinfunction "2_2") (pintype "passive"))
      (node (ref "C25") (pin "2") (pinfunction "2_2") (pintype "passive"))
      (node (ref "C26") (pin "2") (pinfunction "2_2") (pintype "passive"))
      (node (ref "IC2") (pin "10") (pinfunction "VDD_10") (pintype "power_in"))
      (node (ref "IC2") (pin "32") (pinfunction "VDD_32") (pintype "power_in"))
      (node (ref "IC2") (pin "5") (pinfunction "VDD_5") (pintype "power_in"))
      (node (ref "L2") (pin "1") (pinfunction "1_1") (pintype "passive"))
    )
    (net (code "61") (name "Net-(C43-Pad2)") (class "Default")
      (node (ref "C43") (pin "2") (pinfunction "2_2") (pintype "passive"))
      (node (ref "C44") (pin "2") (pinfunction "2_2") (pintype "passive"))
      (node (ref "J1") (pin "2") (pinfunction "2_2") (pintype "bidirectional"))
      (node (ref "R29") (pin "2") (pinfunction "2_2") (pintype "passive"))
    )
    (net (code "62") (name "Net-(C46-Pad2)") (class "Default")
      (node (ref "C46") (pin "2") (pinfunction "2_2") (pintype "passive"))
      (node (ref "C47") (pin "2") (pinfunction "2_2") (pintype "passive"))
      (node (ref "J2") (pin "2") (pinfunction "2_2") (pintype "bidirectional"))
      (node (ref "R30") (pin "2") (pinfunction "2_2") (pintype "passive"))
    )
    (net (code "63") (name "Net-(C225-Pad1)") (class "Default")
      (node (ref "C225") (pin "1") (pinfunction "1_1") (pintype "passive"))
      (node (ref "C278") (pin "2") (pinfunction "2_2") (pintype "passive"))
      (node (ref "IC10") (pin "1") (pinfunction "IN_1") (pintype "input"))
      (node (ref "IC10") (pin "2") (pinfunction "IN_2") (pintype "input"))
      (node (ref "L35") (pin "2") (pinfunction "2_2") (pintype "passive"))
    )
    (net (code "64") (name "Net-(IC1-VREF)") (class "Default")
      (node (ref "C49") (pin "2") (pinfunction "2_2") (pintype "passive"))
      (node (ref "IC1") (pin "17") (pinfunction "VREF_17") (pintype "input"))
    )
    (net (code "65") (name "Net-(IC1-~{Q8})") (class "Default")
      (node (ref "IC1") (pin "26") (pinfunction "~{Q8}_26") (pintype "output"))
      (node (ref "R7") (pin "1") (pinfunction "1_1") (pintype "passive"))
    )
    (net (code "66") (name "Net-(IC1-~{Q9})") (class "Default")
      (node (ref "IC1") (pin "24") (pinfunction "~{Q9}_24") (pintype "output"))
      (node (ref "R8") (pin "1") (pinfunction "1_1") (pintype "passive"))
    )
    (net (code "67") (name "Net-(IC2-CS_CA)") (class "Default")
      (node (ref "IC2") (pin "21") (pinfunction "CS_CA_21") (pintype "bidirectional"))
      (node (ref "R17") (pin "2") (pinfunction "2_2") (pintype "passive"))
    )
    (net (code "68") (name "Net-(IC2-LOL)") (class "Default")
      (node (ref "IC2") (pin "18") (pinfunction "LOL_18") (pintype "output"))
      (node (ref "T1") (pin "1") (pinfunction "G_1") (pintype "passive"))
    )
    (net (code "69") (name "Net-(IC2-SCL)") (class "Default")
      (node (ref "IC2") (pin "22") (pinfunction "SCL_22") (pintype "input"))
      (node (ref "R237") (pin "2") (pinfunction "2_2") (pintype "passive"))
    )
    (net (code "70") (name "Net-(IC2-SDA_SDO)") (class "Default")
      (node (ref "IC2") (pin "23") (pinfunction "SDA_SDO_23") (pintype "bidirectional"))
      (node (ref "R236") (pin "2") (pinfunction "2_2") (pintype "passive"))
    )
    (net (code "71") (name "Net-(IC2-XA)") (class "Default")
      (node (ref "IC2") (pin "6") (pinfunction "XA_6") (pintype "input"))
      (node (ref "Q1") (pin "3") (pinfunction "X_3") (pintype "passive"))
      (node (ref "TP1") (pin "1") (pinfunction "1_1") (pintype "bidirectional"))
    )
    (net (code "72") (name "Net-(IC2-XB)") (class "Default")
      (node (ref "IC2") (pin "7") (pinfunction "XB_7") (pintype "input"))
      (node (ref "Q1") (pin "1") (pinfunction "X_1") (pintype "passive"))
    )
    (net (code "73") (name "Net-(IC2-~{RST})") (class "Default")
      (node (ref "IC2") (pin "1") (pinfunction "~{RST}_1") (pintype "input"))
      (node (ref "R22") (pin "2") (pinfunction "2_2") (pintype "passive"))
    )
    (net (code "74") (name "Net-(IC3-EN{slash}UV)") (class "Default")
      (node (ref "IC3") (pin "3") (pinfunction "EN/UV_3") (pintype "input"))
      (node (ref "R54") (pin "2") (pinfunction "2_2") (pintype "passive"))
    )
    (net (code "75") (name "Net-(IC3-PGFB)") (class "Default")
      (node (ref "IC3") (pin "6") (pinfunction "PGFB_6") (pintype "input"))
      (node (ref "R248") (pin "1") (pinfunction "1_1") (pintype "passive"))
      (node (ref "R251") (pin "2") (pinfunction "2_2") (pintype "passive"))
    )
    (net (code "76") (name "Net-(IC3-SET)") (class "Default")
      (node (ref "C19") (pin "1") (pinfunction "1_1") (pintype "passive"))
      (node (ref "IC3") (pin "7") (pinfunction "SET_7") (pintype "input"))
      (node (ref "R10") (pin "2") (pinfunction "2_2") (pintype "passive"))
    )
    (net (code "77") (name "Net-(IC10-EN{slash}UV)") (class "Default")
      (node (ref "IC10") (pin "3") (pinfunction "EN/UV_3") (pintype "input"))
      (node (ref "R253") (pin "2") (pinfunction "2_2") (pintype "passive"))
    )
    (net (code "78") (name "Net-(IC10-PGFB)") (class "Default")
      (node (ref "IC10") (pin "6") (pinfunction "PGFB_6") (pintype "input"))
      (node (ref "R254") (pin "1") (pinfunction "1_1") (pintype "passive"))
      (node (ref "R256") (pin "1") (pinfunction "1_1") (pintype "passive"))
    )
    (net (code "79") (name "Net-(IC10-SET)") (class "Default")
      (node (ref "C286") (pin "1") (pinfunction "1_1") (pintype "passive"))
      (node (ref "IC10") (pin "7") (pinfunction "SET_7") (pintype "input"))
      (node (ref "R255") (pin "2") (pinfunction "2_2") (pintype "passive"))
    )
    (net (code "80") (name "Net-(IC11-EN{slash}UV)") (class "Default")
      (node (ref "IC11") (pin "3") (pinfunction "EN/UV_3") (pintype "input"))
      (node (ref "R56") (pin "2") (pinfunction "2_2") (pintype "passive"))
    )
    (net (code "81") (name "Net-(IC11-PGFB)") (class "Default")
      (node (ref "IC11") (pin "6") (pinfunction "PGFB_6") (pintype "input"))
      (node (ref "R250") (pin "1") (pinfunction "1_1") (pintype "passive"))
      (node (ref "R252") (pin "1") (pinfunction "1_1") (pintype "passive"))
    )
    (net (code "82") (name "Net-(IC11-SET)") (class "Default")
      (node (ref "C45") (pin "1") (pinfunction "1_1") (pintype "passive"))
      (node (ref "IC11") (pin "7") (pinfunction "SET_7") (pintype "input"))
      (node (ref "R25") (pin "2") (pinfunction "2_2") (pintype "passive"))
    )
    (net (code "83") (name "Net-(IC12-B1)") (class "Default")
      (node (ref "IC12") (pin "5") (pinfunction "B1_5") (pintype "bidirectional"))
      (node (ref "R36") (pin "1") (pinfunction "1_1") (pintype "passive"))
      (node (ref "R38") (pin "2") (pinfunction "2_2") (pintype "passive"))
    )
    (net (code "84") (name "Net-(IC12-B2)") (class "Default")
      (node (ref "IC12") (pin "4") (pinfunction "B2_4") (pintype "bidirectional"))
      (node (ref "R97") (pin "1") (pinfunction "1_1") (pintype "passive"))
      (node (ref "R98") (pin "2") (pinfunction "2_2") (pintype "passive"))
    )
    (net (code "85") (name "Net-(LD1-A)") (class "Default")
      (node (ref "LD1") (pin "2") (pinfunction "A_2") (pintype "passive"))
      (node (ref "R15") (pin "1") (pinfunction "1_1") (pintype "passive"))
    )
    (net (code "86") (name "Net-(LD1-C)") (class "Default")
      (node (ref "LD1") (pin "1") (pinfunction "C_1") (pintype "passive"))
      (node (ref "T1") (pin "3") (pinfunction "D_3") (pintype "passive"))
    )
    (net (code "87") (name "Net-(OSC1-NC)") (class "Default")
      (node (ref "OSC1") (pin "1") (pinfunction "NC_1") (pintype "passive"))
      (node (ref "R38") (pin "1") (pinfunction "1_1") (pintype "passive"))
    )
    (net (code "88") (name "Net-(OSC1-OE)") (class "Default")
      (node (ref "OSC1") (pin "2") (pinfunction "OE_2") (pintype "input"))
      (node (ref "R36") (pin "2") (pinfunction "2_2") (pintype "passive"))
    )
    (net (code "89") (name "Net-(OSC1-VDD)") (class "Default")
      (node (ref "C226") (pin "2") (pinfunction "2_2") (pintype "passive"))
      (node (ref "C287") (pin "2") (pinfunction "2_2") (pintype "passive"))
      (node (ref "C288") (pin "2") (pinfunction "2_2") (pintype "passive"))
      (node (ref "L36") (pin "2") (pinfunction "2_2") (pintype "passive"))
      (node (ref "OSC1") (pin "6") (pinfunction "VDD_6") (pintype "power_in"))
    )
    (net (code "90") (name "Net-(OSC3-NC)") (class "Default")
      (node (ref "OSC3") (pin "1") (pinfunction "NC_1") (pintype "passive"))
      (node (ref "R98") (pin "1") (pinfunction "1_1") (pintype "passive"))
    )
    (net (code "91") (name "Net-(OSC3-OE)") (class "Default")
      (node (ref "OSC3") (pin "2") (pinfunction "OE_2") (pintype "input"))
      (node (ref "R97") (pin "2") (pinfunction "2_2") (pintype "passive"))
    )
    (net (code "92") (name "Net-(OSC3-VDD)") (class "Default")
      (node (ref "C289") (pin "2") (pinfunction "2_2") (pintype "passive"))
      (node (ref "C290") (pin "2") (pinfunction "2_2") (pintype "passive"))
      (node (ref "C291") (pin "2") (pinfunction "2_2") (pintype "passive"))
      (node (ref "L37") (pin "2") (pinfunction "2_2") (pintype "passive"))
      (node (ref "OSC3") (pin "6") (pinfunction "VDD_6") (pintype "power_in"))
    )
    (net (code "93") (name "Net-(R10-Pad1)") (class "Default")
      (node (ref "R10") (pin "1") (pinfunction "1_1") (pintype "passive"))
      (node (ref "R28") (pin "2") (pinfunction "2_2") (pintype "passive"))
    )
    (net (code "94") (name "P2V5") (class "Default")
      (node (ref "C296") (pin "2") (pinfunction "2_2") (pintype "passive"))
      (node (ref "R1") (pin "1") (pinfunction "1_1") (pintype "passive"))
      (node (ref "R210") (pin "1") (pinfunction "1_1") (pintype "passive"))
      (node (ref "R253") (pin "1") (pinfunction "1_1") (pintype "passive"))
      (node (ref "R34") (pin "2") (pinfunction "2_2") (pintype "passive"))
      (node (ref "R35") (pin "2") (pinfunction "2_2") (pintype "passive"))
      (node (ref "R41") (pin "2") (pinfunction "2_2") (pintype "passive"))
      (node (ref "R50") (pin "2") (pinfunction "2_2") (pintype "passive"))
      (node (ref "R56") (pin "1") (pinfunction "1_1") (pintype "passive"))
    )
    (net (code "95") (name "P2V5_LDO") (class "Default")
      (node (ref "C16") (pin "2") (pinfunction "2_2") (pintype "passive"))
      (node (ref "C29") (pin "2") (pinfunction "2_2") (pintype "passive"))
      (node (ref "IC12") (pin "6") (pinfunction "VCCB_6") (pintype "power_in"))
      (node (ref "IC3") (pin "10") (pinfunction "OUT_10") (pintype "output"))
      (node (ref "IC3") (pin "9") (pinfunction "OUTS_9") (pintype "output"))
      (node (ref "L36") (pin "1") (pinfunction "1_1") (pintype "passive"))
      (node (ref "L37") (pin "1") (pinfunction "1_1") (pintype "passive"))
      (node (ref "R248") (pin "2") (pinfunction "2_2") (pintype "passive"))
      (node (ref "TP4") (pin "1") (pinfunction "1_1") (pintype "bidirectional"))
    )
    (net (code "96") (name "P3V3") (class "Default")
      (node (ref "C28") (pin "2") (pinfunction "2_2") (pintype "passive"))
      (node (ref "C298") (pin "2") (pinfunction "2_2") (pintype "passive"))
      (node (ref "IC12") (pin "1") (pinfunction "DIR2_1") (pintype "input"))
      (node (ref "IC12") (pin "10") (pinfunction "DIR1_10") (pintype "input"))
      (node (ref "IC12") (pin "7") (pinfunction "VCCA_7") (pintype "power_in"))
      (node (ref "L3") (pin "1") (pinfunction "1_1") (pintype "passive"))
      (node (ref "R244") (pin "2") (pinfunction "2_2") (pintype "passive"))
      (node (ref "R245") (pin "2") (pinfunction "2_2") (pintype "passive"))
    )
    (net (code "97") (name "P3V3_ADCLK") (class "Default")
      (node (ref "C190") (pin "2") (pinfunction "2_2") (pintype "passive"))
      (node (ref "C191") (pin "2") (pinfunction "2_2") (pintype "passive"))
      (node (ref "C234") (pin "2") (pinfunction "2_2") (pintype "passive"))
      (node (ref "C239") (pin "2") (pinfunction "2_2") (pintype "passive"))
      (node (ref "C241") (pin "2") (pinfunction "2_2") (pintype "passive"))
      (node (ref "C242") (pin "2") (pinfunction "2_2") (pintype "passive"))
      (node (ref "C243") (pin "2") (pinfunction "2_2") (pintype "passive"))
      (node (ref "IC1") (pin "12") (pinfunction "VDD_12") (pintype "power_in"))
      (node (ref "IC1") (pin "34") (pinfunction "VDDOB_34") (pintype "output"))
      (node (ref "IC1") (pin "44") (pinfunction "VDDOA_44") (pintype "output"))
      (node (ref "L29") (pin "1") (pinfunction "1_1") (pintype "passive"))
    )
    (net (code "98") (name "P3V3_LDO1") (class "Default")
      (node (ref "C17") (pin "2") (pinfunction "2_2") (pintype "passive"))
      (node (ref "IC11") (pin "10") (pinfunction "OUT_10") (pintype "output"))
      (node (ref "IC11") (pin "9") (pinfunction "OUTS_9") (pintype "output"))
      (node (ref "L2") (pin "2") (pinfunction "2_2") (pintype "passive"))
      (node (ref "R15") (pin "2") (pinfunction "2_2") (pintype "passive"))
      (node (ref "R22") (pin "1") (pinfunction "1_1") (pintype "passive"))
      (node (ref "R250") (pin "2") (pinfunction "2_2") (pintype "passive"))
      (node (ref "TP20") (pin "1") (pinfunction "1_1") (pintype "bidirectional"))
    )
    (net (code "99") (name "P3V3_LDO2") (class "Default")
      (node (ref "C279") (pin "2") (pinfunction "2_2") (pintype "passive"))
      (node (ref "IC10") (pin "10") (pinfunction "OUT_10") (pintype "output"))
      (node (ref "IC10") (pin "9") (pinfunction "OUTS_9") (pintype "output"))
      (node (ref "L29") (pin "2") (pinfunction "2_2") (pintype "passive"))
      (node (ref "R242") (pin "2") (pinfunction "2_2") (pintype "passive"))
      (node (ref "R254") (pin "2") (pinfunction "2_2") (pintype "passive"))
      (node (ref "R4") (pin "2") (pinfunction "2_2") (pintype "passive"))
      (node (ref "R54") (pin "1") (pinfunction "1_1") (pintype "passive"))
      (node (ref "TP25") (pin "1") (pinfunction "1_1") (pintype "bidirectional"))
    )
    (net (code "100") (name "P5V0_CLK") (class "Default")
      (node (ref "C199") (pin "2") (pinfunction "2_2") (pintype "passive"))
      (node (ref "C3") (pin "2") (pinfunction "2_2") (pintype "passive"))
      (node (ref "L1") (pin "1") (pinfunction "1_1") (pintype "passive"))
    )
    (net (code "101") (name "P5V0_CLKa") (class "Default")
      (node (ref "C18") (pin "2") (pinfunction "2_2") (pintype "passive"))
      (node (ref "C38") (pin "2") (pinfunction "2_2") (pintype "passive"))
      (node (ref "L1") (pin "2") (pinfunction "2_2") (pintype "passive"))
      (node (ref "L23") (pin "1") (pinfunction "1_1") (pintype "passive"))
      (node (ref "L35") (pin "1") (pinfunction "1_1") (pintype "passive"))
    )
    (net (code "102") (name "unconnected-(IC1-DIVA-Pad1)") (class "Default")
      (node (ref "IC1") (pin "1") (pinfunction "DIVA_1") (pintype "input+no_connect"))
    )
    (net (code "103") (name "unconnected-(IC1-DIVB-Pad33)") (class "Default")
      (node (ref "IC1") (pin "33") (pinfunction "DIVB_33") (pintype "input+no_connect"))
    )
    (net (code "104") (name "unconnected-(IC1-NC-Pad11)") (class "Default")
      (node (ref "IC1") (pin "11") (pinfunction "NC_11") (pintype "passive+no_connect"))
    )
    (net (code "105") (name "unconnected-(IC1-NC-Pad13)") (class "Default")
      (node (ref "IC1") (pin "13") (pinfunction "NC_13") (pintype "passive+no_connect"))
    )
    (net (code "106") (name "unconnected-(IC1-NC-Pad21)") (class "Default")
      (node (ref "IC1") (pin "21") (pinfunction "NC_21") (pintype "passive+no_connect"))
    )
    (net (code "107") (name "unconnected-(IC1-NC-Pad28)") (class "Default")
      (node (ref "IC1") (pin "28") (pinfunction "NC_28") (pintype "passive+no_connect"))
    )
    (net (code "108") (name "unconnected-(IC1-Q1-Pad8)") (class "Default")
      (node (ref "IC1") (pin "8") (pinfunction "Q1_8") (pintype "output+no_connect"))
    )
    (net (code "109") (name "unconnected-(IC1-Q7-Pad30)") (class "Default")
      (node (ref "IC1") (pin "30") (pinfunction "Q7_30") (pintype "output+no_connect"))
    )
    (net (code "110") (name "unconnected-(IC1-~{Q1}-Pad7)") (class "Default")
      (node (ref "IC1") (pin "7") (pinfunction "~{Q1}_7") (pintype "output+no_connect"))
    )
    (net (code "111") (name "unconnected-(IC1-~{Q7}-Pad29)") (class "Default")
      (node (ref "IC1") (pin "29") (pinfunction "~{Q7}_29") (pintype "output+no_connect"))
    )
    (net (code "112") (name "unconnected-(IC2-C2B-Pad4)") (class "Default")
      (node (ref "IC2") (pin "4") (pinfunction "C2B_4") (pintype "output+no_connect"))
    )
    (net (code "113") (name "unconnected-(IC2-CKIN2+-Pad12)") (class "Default")
      (node (ref "IC2") (pin "12") (pinfunction "CKIN2+_12") (pintype "input+no_connect"))
    )
    (net (code "114") (name "unconnected-(IC2-CKIN2--Pad13)") (class "Default")
      (node (ref "IC2") (pin "13") (pinfunction "CKIN2-_13") (pintype "input+no_connect"))
    )
    (net (code "115") (name "unconnected-(IC2-CKOUT2+-Pad35)") (class "Default")
      (node (ref "IC2") (pin "35") (pinfunction "CKOUT2+_35") (pintype "output+no_connect"))
    )
    (net (code "116") (name "unconnected-(IC2-CKOUT2--Pad34)") (class "Default")
      (node (ref "IC2") (pin "34") (pinfunction "CKOUT2-_34") (pintype "output+no_connect"))
    )
    (net (code "117") (name "unconnected-(IC2-INT_C1B-Pad3)") (class "Default")
      (node (ref "IC2") (pin "3") (pinfunction "INT_C1B_3") (pintype "output+no_connect"))
    )
    (net (code "118") (name "unconnected-(IC2-NC-Pad2)") (class "Default")
      (node (ref "IC2") (pin "2") (pinfunction "NC_2") (pintype "passive+no_connect"))
    )
    (net (code "119") (name "unconnected-(IC2-NC-Pad9)") (class "Default")
      (node (ref "IC2") (pin "9") (pinfunction "NC_9") (pintype "passive+no_connect"))
    )
    (net (code "120") (name "unconnected-(IC2-NC-Pad14)") (class "Default")
      (node (ref "IC2") (pin "14") (pinfunction "NC_14") (pintype "passive+no_connect"))
    )
    (net (code "121") (name "unconnected-(IC2-NC-Pad30)") (class "Default")
      (node (ref "IC2") (pin "30") (pinfunction "NC_30") (pintype "passive+no_connect"))
    )
    (net (code "122") (name "unconnected-(IC2-NC-Pad33)") (class "Default")
      (node (ref "IC2") (pin "33") (pinfunction "NC_33") (pintype "passive+no_connect"))
    )
    (net (code "123") (name "unconnected-(IC2-RATE0-Pad11)") (class "Default")
      (node (ref "IC2") (pin "11") (pinfunction "RATE0_11") (pintype "input+no_connect"))
    )
    (net (code "124") (name "unconnected-(IC2-RATE1-Pad15)") (class "Default")
      (node (ref "IC2") (pin "15") (pinfunction "RATE1_15") (pintype "input+no_connect"))
    )
    (net (code "125") (name "unconnected-(IC2-SDI-Pad27)") (class "Default")
      (node (ref "IC2") (pin "27") (pinfunction "SDI_27") (pintype "input+no_connect"))
    )
    (net (code "126") (name "unconnected-(IC3-PG-Pad4)") (class "Default")
      (node (ref "IC3") (pin "4") (pinfunction "PG_4") (pintype "output+no_connect"))
    )
    (net (code "127") (name "unconnected-(IC10-PG-Pad4)") (class "Default")
      (node (ref "IC10") (pin "4") (pinfunction "PG_4") (pintype "output+no_connect"))
    )
    (net (code "128") (name "unconnected-(IC11-PG-Pad4)") (class "Default")
      (node (ref "IC11") (pin "4") (pinfunction "PG_4") (pintype "output+no_connect"))
    )
  )
)
